# WordClock.net
KiCad netlist of a schematic drawn in EAGLE
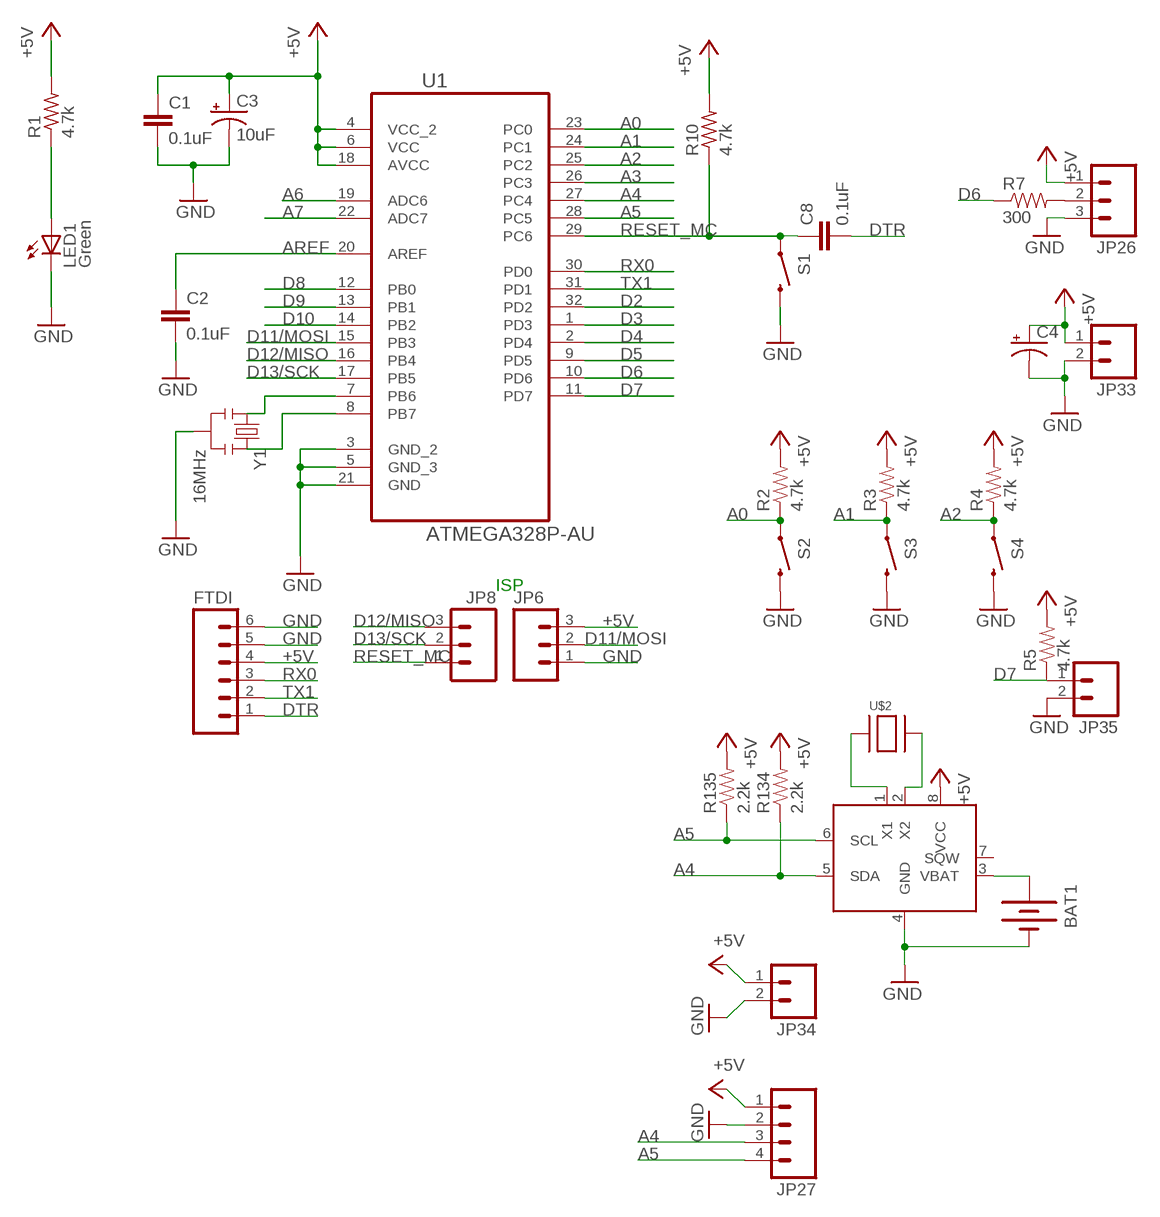
[diagram p0: schematic, sheet 1, part 1 of 2]
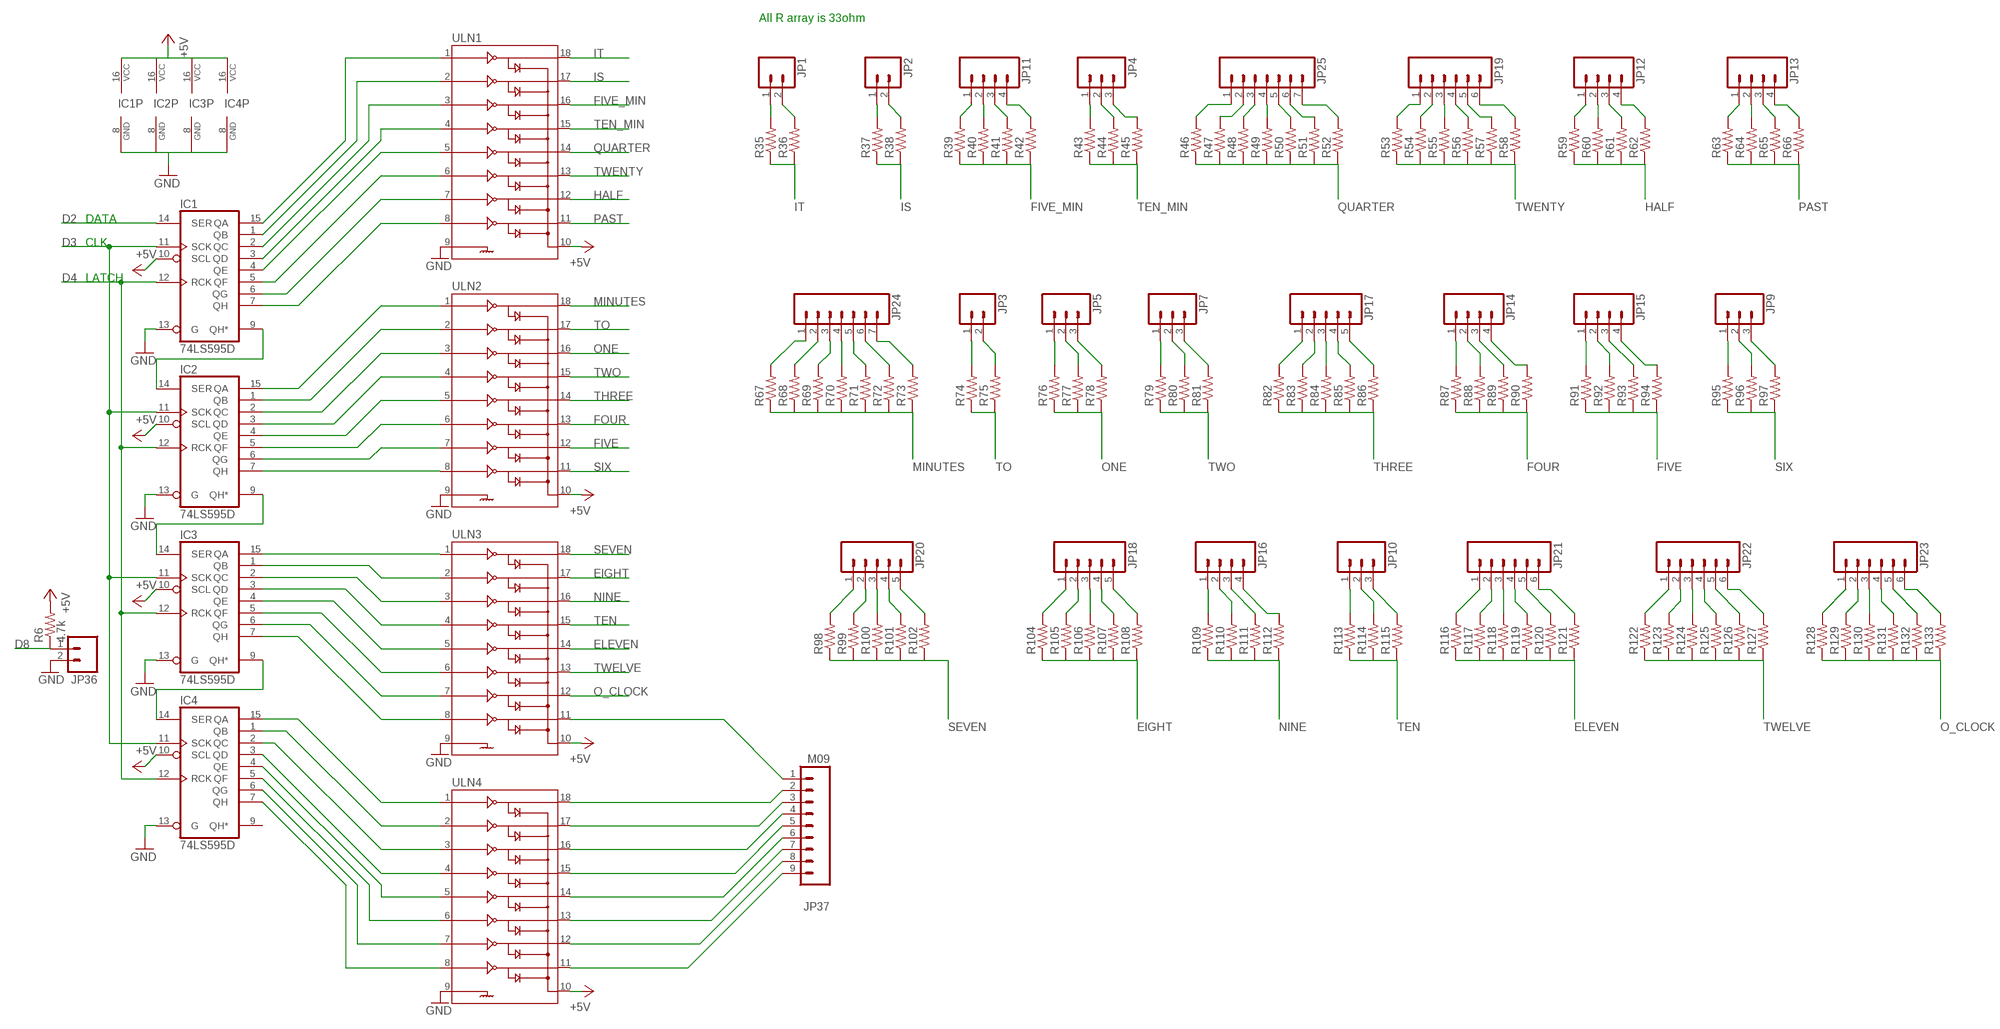
[diagram p1: schematic, sheet 1, part 2 of 2]

(export (version "E")
  (design (tool "Eeschema 10.0.6"))
  (components
    (comp (ref "BAT1")
      (value "BATTERY12MM")
      (footprint "eagle-import:BATTCON_12MM")
      (libsource (lib "eagle-import") (part "BATTERY12MM"))
    )
    (comp (ref "C1")
      (value "0.1uF")
      (footprint "eagle-import:0402-CAP")
      (libsource (lib "eagle-import") (part "CAP0402-CAP"))
    )
    (comp (ref "C2")
      (value "0.1uF")
      (footprint "eagle-import:0402-CAP")
      (libsource (lib "eagle-import") (part "CAP0402-CAP"))
    )
    (comp (ref "C3")
      (value "10uF")
      (footprint "eagle-import:EIA3216")
      (libsource (lib "eagle-import") (part "CAP_POL1206"))
    )
    (comp (ref "C4")
      (value "CPOL-USF")
      (footprint "eagle-import:PANASONIC_F")
      (libsource (lib "eagle-import") (part "CPOL-USF"))
    )
    (comp (ref "C8")
      (value "0.1uF")
      (footprint "eagle-import:0402-CAP")
      (libsource (lib "eagle-import") (part "CAP0402-CAP"))
    )
    (comp (ref "FTDI")
      (value "M06SIP")
      (footprint "eagle-import:1X06")
      (libsource (lib "eagle-import") (part "M06SIP"))
    )
    (comp (ref "IC1")
      (value "74LS595D")
      (footprint "eagle-import:SO16")
      (libsource (lib "eagle-import") (part "74595DLS"))
    )
    (comp (ref "IC2")
      (value "74LS595D")
      (footprint "eagle-import:SO16")
      (libsource (lib "eagle-import") (part "74595DLS"))
    )
    (comp (ref "IC3")
      (value "74LS595D")
      (footprint "eagle-import:SO16")
      (libsource (lib "eagle-import") (part "74595DLS"))
    )
    (comp (ref "IC4")
      (value "74LS595D")
      (footprint "eagle-import:SO16")
      (libsource (lib "eagle-import") (part "74595DLS"))
    )
    (comp (ref "JP1")
      (value "M02PTH")
      (footprint "eagle-import:1X02")
      (libsource (lib "eagle-import") (part "M02PTH"))
    )
    (comp (ref "JP2")
      (value "M02PTH")
      (footprint "eagle-import:1X02")
      (libsource (lib "eagle-import") (part "M02PTH"))
    )
    (comp (ref "JP3")
      (value "M02PTH")
      (footprint "eagle-import:1X02")
      (libsource (lib "eagle-import") (part "M02PTH"))
    )
    (comp (ref "JP4")
      (value "M03PTH")
      (footprint "eagle-import:1X03")
      (libsource (lib "eagle-import") (part "M03PTH"))
    )
    (comp (ref "JP5")
      (value "M03PTH")
      (footprint "eagle-import:1X03")
      (libsource (lib "eagle-import") (part "M03PTH"))
    )
    (comp (ref "JP6")
      (value "M03PTH")
      (footprint "eagle-import:1X03")
      (libsource (lib "eagle-import") (part "M03PTH"))
    )
    (comp (ref "JP7")
      (value "M03PTH")
      (footprint "eagle-import:1X03")
      (libsource (lib "eagle-import") (part "M03PTH"))
    )
    (comp (ref "JP8")
      (value "M03PTH")
      (footprint "eagle-import:1X03")
      (libsource (lib "eagle-import") (part "M03PTH"))
    )
    (comp (ref "JP9")
      (value "M03PTH")
      (footprint "eagle-import:1X03")
      (libsource (lib "eagle-import") (part "M03PTH"))
    )
    (comp (ref "JP10")
      (value "M03PTH")
      (footprint "eagle-import:1X03")
      (libsource (lib "eagle-import") (part "M03PTH"))
    )
    (comp (ref "JP11")
      (value "M04PTH")
      (footprint "eagle-import:1X04")
      (libsource (lib "eagle-import") (part "M04PTH"))
    )
    (comp (ref "JP12")
      (value "M04PTH")
      (footprint "eagle-import:1X04")
      (libsource (lib "eagle-import") (part "M04PTH"))
    )
    (comp (ref "JP13")
      (value "M04PTH")
      (footprint "eagle-import:1X04")
      (libsource (lib "eagle-import") (part "M04PTH"))
    )
    (comp (ref "JP14")
      (value "M04PTH")
      (footprint "eagle-import:1X04")
      (libsource (lib "eagle-import") (part "M04PTH"))
    )
    (comp (ref "JP15")
      (value "M04PTH")
      (footprint "eagle-import:1X04")
      (libsource (lib "eagle-import") (part "M04PTH"))
    )
    (comp (ref "JP16")
      (value "M04PTH")
      (footprint "eagle-import:1X04")
      (libsource (lib "eagle-import") (part "M04PTH"))
    )
    (comp (ref "JP17")
      (value "M05PTH")
      (footprint "eagle-import:1X05")
      (libsource (lib "eagle-import") (part "M05PTH"))
    )
    (comp (ref "JP18")
      (value "M05PTH")
      (footprint "eagle-import:1X05")
      (libsource (lib "eagle-import") (part "M05PTH"))
    )
    (comp (ref "JP19")
      (value "M06SIP")
      (footprint "eagle-import:1X06")
      (libsource (lib "eagle-import") (part "M06SIP"))
    )
    (comp (ref "JP20")
      (value "M05PTH")
      (footprint "eagle-import:1X05")
      (libsource (lib "eagle-import") (part "M05PTH"))
    )
    (comp (ref "JP21")
      (value "M06SIP")
      (footprint "eagle-import:1X06")
      (libsource (lib "eagle-import") (part "M06SIP"))
    )
    (comp (ref "JP22")
      (value "M06SIP")
      (footprint "eagle-import:1X06")
      (libsource (lib "eagle-import") (part "M06SIP"))
    )
    (comp (ref "JP23")
      (value "M06SIP")
      (footprint "eagle-import:1X06")
      (libsource (lib "eagle-import") (part "M06SIP"))
    )
    (comp (ref "JP24")
      (value "M07")
      (footprint "eagle-import:1X07")
      (libsource (lib "eagle-import") (part "M07"))
    )
    (comp (ref "JP25")
      (value "M07")
      (footprint "eagle-import:1X07")
      (libsource (lib "eagle-import") (part "M07"))
    )
    (comp (ref "JP26")
      (value "M03PTH")
      (footprint "eagle-import:1X03")
      (libsource (lib "eagle-import") (part "M03PTH"))
    )
    (comp (ref "JP27")
      (value "M04PTH")
      (footprint "eagle-import:1X04")
      (libsource (lib "eagle-import") (part "M04PTH"))
    )
    (comp (ref "JP33")
      (value "M02PTH")
      (footprint "eagle-import:1X02")
      (libsource (lib "eagle-import") (part "M02PTH"))
    )
    (comp (ref "JP34")
      (value "M02PTH")
      (footprint "eagle-import:1X02")
      (libsource (lib "eagle-import") (part "M02PTH"))
    )
    (comp (ref "JP35")
      (value "M02PTH")
      (footprint "eagle-import:1X02")
      (libsource (lib "eagle-import") (part "M02PTH"))
    )
    (comp (ref "JP36")
      (value "M02PTH")
      (footprint "eagle-import:1X02")
      (libsource (lib "eagle-import") (part "M02PTH"))
    )
    (comp (ref "JP37")
      (value "M09")
      (footprint "eagle-import:1X09")
      (libsource (lib "eagle-import") (part "M09"))
    )
    (comp (ref "LED1")
      (value "Green")
      (footprint "eagle-import:LED-0603")
      (libsource (lib "eagle-import") (part "LED0603"))
    )
    (comp (ref "R1")
      (value "4.7k")
      (footprint "eagle-import:R0603")
      (libsource (lib "eagle-import") (part "R-US_R0603"))
    )
    (comp (ref "R2")
      (value "4.7k")
      (footprint "eagle-import:0603-RES")
      (libsource (lib "eagle-import") (part "RESISTOR0603-RES"))
    )
    (comp (ref "R3")
      (value "4.7k")
      (footprint "eagle-import:0603-RES")
      (libsource (lib "eagle-import") (part "RESISTOR0603-RES"))
    )
    (comp (ref "R4")
      (value "4.7k")
      (footprint "eagle-import:0603-RES")
      (libsource (lib "eagle-import") (part "RESISTOR0603-RES"))
    )
    (comp (ref "R5")
      (value "4.7k")
      (footprint "eagle-import:0603-RES")
      (libsource (lib "eagle-import") (part "RESISTOR0603-RES"))
    )
    (comp (ref "R6")
      (value "4.7k")
      (footprint "eagle-import:0603-RES")
      (libsource (lib "eagle-import") (part "RESISTOR0603-RES"))
    )
    (comp (ref "R7")
      (value "300")
      (footprint "eagle-import:0603-RES")
      (libsource (lib "eagle-import") (part "RESISTOR0603-RES"))
    )
    (comp (ref "R10")
      (value "4.7k")
      (footprint "eagle-import:R0603")
      (libsource (lib "eagle-import") (part "R-US_R0603"))
    )
    (comp (ref "R35")
      (value "RESISTOR0603-RES")
      (footprint "eagle-import:0603-RES")
      (libsource (lib "eagle-import") (part "RESISTOR0603-RES"))
    )
    (comp (ref "R36")
      (value "RESISTOR0603-RES")
      (footprint "eagle-import:0603-RES")
      (libsource (lib "eagle-import") (part "RESISTOR0603-RES"))
    )
    (comp (ref "R37")
      (value "RESISTOR0603-RES")
      (footprint "eagle-import:0603-RES")
      (libsource (lib "eagle-import") (part "RESISTOR0603-RES"))
    )
    (comp (ref "R38")
      (value "RESISTOR0603-RES")
      (footprint "eagle-import:0603-RES")
      (libsource (lib "eagle-import") (part "RESISTOR0603-RES"))
    )
    (comp (ref "R39")
      (value "RESISTOR0603-RES")
      (footprint "eagle-import:0603-RES")
      (libsource (lib "eagle-import") (part "RESISTOR0603-RES"))
    )
    (comp (ref "R40")
      (value "RESISTOR0603-RES")
      (footprint "eagle-import:0603-RES")
      (libsource (lib "eagle-import") (part "RESISTOR0603-RES"))
    )
    (comp (ref "R41")
      (value "RESISTOR0603-RES")
      (footprint "eagle-import:0603-RES")
      (libsource (lib "eagle-import") (part "RESISTOR0603-RES"))
    )
    (comp (ref "R42")
      (value "RESISTOR0603-RES")
      (footprint "eagle-import:0603-RES")
      (libsource (lib "eagle-import") (part "RESISTOR0603-RES"))
    )
    (comp (ref "R43")
      (value "RESISTOR0603-RES")
      (footprint "eagle-import:0603-RES")
      (libsource (lib "eagle-import") (part "RESISTOR0603-RES"))
    )
    (comp (ref "R44")
      (value "RESISTOR0603-RES")
      (footprint "eagle-import:0603-RES")
      (libsource (lib "eagle-import") (part "RESISTOR0603-RES"))
    )
    (comp (ref "R45")
      (value "RESISTOR0603-RES")
      (footprint "eagle-import:0603-RES")
      (libsource (lib "eagle-import") (part "RESISTOR0603-RES"))
    )
    (comp (ref "R46")
      (value "RESISTOR0603-RES")
      (footprint "eagle-import:0603-RES")
      (libsource (lib "eagle-import") (part "RESISTOR0603-RES"))
    )
    (comp (ref "R47")
      (value "RESISTOR0603-RES")
      (footprint "eagle-import:0603-RES")
      (libsource (lib "eagle-import") (part "RESISTOR0603-RES"))
    )
    (comp (ref "R48")
      (value "RESISTOR0603-RES")
      (footprint "eagle-import:0603-RES")
      (libsource (lib "eagle-import") (part "RESISTOR0603-RES"))
    )
    (comp (ref "R49")
      (value "RESISTOR0603-RES")
      (footprint "eagle-import:0603-RES")
      (libsource (lib "eagle-import") (part "RESISTOR0603-RES"))
    )
    (comp (ref "R50")
      (value "RESISTOR0603-RES")
      (footprint "eagle-import:0603-RES")
      (libsource (lib "eagle-import") (part "RESISTOR0603-RES"))
    )
    (comp (ref "R51")
      (value "RESISTOR0603-RES")
      (footprint "eagle-import:0603-RES")
      (libsource (lib "eagle-import") (part "RESISTOR0603-RES"))
    )
    (comp (ref "R52")
      (value "RESISTOR0603-RES")
      (footprint "eagle-import:0603-RES")
      (libsource (lib "eagle-import") (part "RESISTOR0603-RES"))
    )
    (comp (ref "R53")
      (value "RESISTOR0603-RES")
      (footprint "eagle-import:0603-RES")
      (libsource (lib "eagle-import") (part "RESISTOR0603-RES"))
    )
    (comp (ref "R54")
      (value "RESISTOR0603-RES")
      (footprint "eagle-import:0603-RES")
      (libsource (lib "eagle-import") (part "RESISTOR0603-RES"))
    )
    (comp (ref "R55")
      (value "RESISTOR0603-RES")
      (footprint "eagle-import:0603-RES")
      (libsource (lib "eagle-import") (part "RESISTOR0603-RES"))
    )
    (comp (ref "R56")
      (value "RESISTOR0603-RES")
      (footprint "eagle-import:0603-RES")
      (libsource (lib "eagle-import") (part "RESISTOR0603-RES"))
    )
    (comp (ref "R57")
      (value "RESISTOR0603-RES")
      (footprint "eagle-import:0603-RES")
      (libsource (lib "eagle-import") (part "RESISTOR0603-RES"))
    )
    (comp (ref "R58")
      (value "RESISTOR0603-RES")
      (footprint "eagle-import:0603-RES")
      (libsource (lib "eagle-import") (part "RESISTOR0603-RES"))
    )
    (comp (ref "R59")
      (value "RESISTOR0603-RES")
      (footprint "eagle-import:0603-RES")
      (libsource (lib "eagle-import") (part "RESISTOR0603-RES"))
    )
    (comp (ref "R60")
      (value "RESISTOR0603-RES")
      (footprint "eagle-import:0603-RES")
      (libsource (lib "eagle-import") (part "RESISTOR0603-RES"))
    )
    (comp (ref "R61")
      (value "RESISTOR0603-RES")
      (footprint "eagle-import:0603-RES")
      (libsource (lib "eagle-import") (part "RESISTOR0603-RES"))
    )
    (comp (ref "R62")
      (value "RESISTOR0603-RES")
      (footprint "eagle-import:0603-RES")
      (libsource (lib "eagle-import") (part "RESISTOR0603-RES"))
    )
    (comp (ref "R63")
      (value "RESISTOR0603-RES")
      (footprint "eagle-import:0603-RES")
      (libsource (lib "eagle-import") (part "RESISTOR0603-RES"))
    )
    (comp (ref "R64")
      (value "RESISTOR0603-RES")
      (footprint "eagle-import:0603-RES")
      (libsource (lib "eagle-import") (part "RESISTOR0603-RES"))
    )
    (comp (ref "R65")
      (value "RESISTOR0603-RES")
      (footprint "eagle-import:0603-RES")
      (libsource (lib "eagle-import") (part "RESISTOR0603-RES"))
    )
    (comp (ref "R66")
      (value "RESISTOR0603-RES")
      (footprint "eagle-import:0603-RES")
      (libsource (lib "eagle-import") (part "RESISTOR0603-RES"))
    )
    (comp (ref "R67")
      (value "RESISTOR0603-RES")
      (footprint "eagle-import:0603-RES")
      (libsource (lib "eagle-import") (part "RESISTOR0603-RES"))
    )
    (comp (ref "R68")
      (value "RESISTOR0603-RES")
      (footprint "eagle-import:0603-RES")
      (libsource (lib "eagle-import") (part "RESISTOR0603-RES"))
    )
    (comp (ref "R69")
      (value "RESISTOR0603-RES")
      (footprint "eagle-import:0603-RES")
      (libsource (lib "eagle-import") (part "RESISTOR0603-RES"))
    )
    (comp (ref "R70")
      (value "RESISTOR0603-RES")
      (footprint "eagle-import:0603-RES")
      (libsource (lib "eagle-import") (part "RESISTOR0603-RES"))
    )
    (comp (ref "R71")
      (value "RESISTOR0603-RES")
      (footprint "eagle-import:0603-RES")
      (libsource (lib "eagle-import") (part "RESISTOR0603-RES"))
    )
    (comp (ref "R72")
      (value "RESISTOR0603-RES")
      (footprint "eagle-import:0603-RES")
      (libsource (lib "eagle-import") (part "RESISTOR0603-RES"))
    )
    (comp (ref "R73")
      (value "RESISTOR0603-RES")
      (footprint "eagle-import:0603-RES")
      (libsource (lib "eagle-import") (part "RESISTOR0603-RES"))
    )
    (comp (ref "R74")
      (value "RESISTOR0603-RES")
      (footprint "eagle-import:0603-RES")
      (libsource (lib "eagle-import") (part "RESISTOR0603-RES"))
    )
    (comp (ref "R75")
      (value "RESISTOR0603-RES")
      (footprint "eagle-import:0603-RES")
      (libsource (lib "eagle-import") (part "RESISTOR0603-RES"))
    )
    (comp (ref "R76")
      (value "RESISTOR0603-RES")
      (footprint "eagle-import:0603-RES")
      (libsource (lib "eagle-import") (part "RESISTOR0603-RES"))
    )
    (comp (ref "R77")
      (value "RESISTOR0603-RES")
      (footprint "eagle-import:0603-RES")
      (libsource (lib "eagle-import") (part "RESISTOR0603-RES"))
    )
    (comp (ref "R78")
      (value "RESISTOR0603-RES")
      (footprint "eagle-import:0603-RES")
      (libsource (lib "eagle-import") (part "RESISTOR0603-RES"))
    )
    (comp (ref "R79")
      (value "RESISTOR0603-RES")
      (footprint "eagle-import:0603-RES")
      (libsource (lib "eagle-import") (part "RESISTOR0603-RES"))
    )
    (comp (ref "R80")
      (value "RESISTOR0603-RES")
      (footprint "eagle-import:0603-RES")
      (libsource (lib "eagle-import") (part "RESISTOR0603-RES"))
    )
    (comp (ref "R81")
      (value "RESISTOR0603-RES")
      (footprint "eagle-import:0603-RES")
      (libsource (lib "eagle-import") (part "RESISTOR0603-RES"))
    )
    (comp (ref "R82")
      (value "RESISTOR0603-RES")
      (footprint "eagle-import:0603-RES")
      (libsource (lib "eagle-import") (part "RESISTOR0603-RES"))
    )
    (comp (ref "R83")
      (value "RESISTOR0603-RES")
      (footprint "eagle-import:0603-RES")
      (libsource (lib "eagle-import") (part "RESISTOR0603-RES"))
    )
    (comp (ref "R84")
      (value "RESISTOR0603-RES")
      (footprint "eagle-import:0603-RES")
      (libsource (lib "eagle-import") (part "RESISTOR0603-RES"))
    )
    (comp (ref "R85")
      (value "RESISTOR0603-RES")
      (footprint "eagle-import:0603-RES")
      (libsource (lib "eagle-import") (part "RESISTOR0603-RES"))
    )
    (comp (ref "R86")
      (value "RESISTOR0603-RES")
      (footprint "eagle-import:0603-RES")
      (libsource (lib "eagle-import") (part "RESISTOR0603-RES"))
    )
    (comp (ref "R87")
      (value "RESISTOR0603-RES")
      (footprint "eagle-import:0603-RES")
      (libsource (lib "eagle-import") (part "RESISTOR0603-RES"))
    )
    (comp (ref "R88")
      (value "RESISTOR0603-RES")
      (footprint "eagle-import:0603-RES")
      (libsource (lib "eagle-import") (part "RESISTOR0603-RES"))
    )
    (comp (ref "R89")
      (value "RESISTOR0603-RES")
      (footprint "eagle-import:0603-RES")
      (libsource (lib "eagle-import") (part "RESISTOR0603-RES"))
    )
    (comp (ref "R90")
      (value "RESISTOR0603-RES")
      (footprint "eagle-import:0603-RES")
      (libsource (lib "eagle-import") (part "RESISTOR0603-RES"))
    )
    (comp (ref "R91")
      (value "RESISTOR0603-RES")
      (footprint "eagle-import:0603-RES")
      (libsource (lib "eagle-import") (part "RESISTOR0603-RES"))
    )
    (comp (ref "R92")
      (value "RESISTOR0603-RES")
      (footprint "eagle-import:0603-RES")
      (libsource (lib "eagle-import") (part "RESISTOR0603-RES"))
    )
    (comp (ref "R93")
      (value "RESISTOR0603-RES")
      (footprint "eagle-import:0603-RES")
      (libsource (lib "eagle-import") (part "RESISTOR0603-RES"))
    )
    (comp (ref "R94")
      (value "RESISTOR0603-RES")
      (footprint "eagle-import:0603-RES")
      (libsource (lib "eagle-import") (part "RESISTOR0603-RES"))
    )
    (comp (ref "R95")
      (value "RESISTOR0603-RES")
      (footprint "eagle-import:0603-RES")
      (libsource (lib "eagle-import") (part "RESISTOR0603-RES"))
    )
    (comp (ref "R96")
      (value "RESISTOR0603-RES")
      (footprint "eagle-import:0603-RES")
      (libsource (lib "eagle-import") (part "RESISTOR0603-RES"))
    )
    (comp (ref "R97")
      (value "RESISTOR0603-RES")
      (footprint "eagle-import:0603-RES")
      (libsource (lib "eagle-import") (part "RESISTOR0603-RES"))
    )
    (comp (ref "R98")
      (value "RESISTOR0603-RES")
      (footprint "eagle-import:0603-RES")
      (libsource (lib "eagle-import") (part "RESISTOR0603-RES"))
    )
    (comp (ref "R99")
      (value "RESISTOR0603-RES")
      (footprint "eagle-import:0603-RES")
      (libsource (lib "eagle-import") (part "RESISTOR0603-RES"))
    )
    (comp (ref "R100")
      (value "RESISTOR0603-RES")
      (footprint "eagle-import:0603-RES")
      (libsource (lib "eagle-import") (part "RESISTOR0603-RES"))
    )
    (comp (ref "R101")
      (value "RESISTOR0603-RES")
      (footprint "eagle-import:0603-RES")
      (libsource (lib "eagle-import") (part "RESISTOR0603-RES"))
    )
    (comp (ref "R102")
      (value "RESISTOR0603-RES")
      (footprint "eagle-import:0603-RES")
      (libsource (lib "eagle-import") (part "RESISTOR0603-RES"))
    )
    (comp (ref "R104")
      (value "RESISTOR0603-RES")
      (footprint "eagle-import:0603-RES")
      (libsource (lib "eagle-import") (part "RESISTOR0603-RES"))
    )
    (comp (ref "R105")
      (value "RESISTOR0603-RES")
      (footprint "eagle-import:0603-RES")
      (libsource (lib "eagle-import") (part "RESISTOR0603-RES"))
    )
    (comp (ref "R106")
      (value "RESISTOR0603-RES")
      (footprint "eagle-import:0603-RES")
      (libsource (lib "eagle-import") (part "RESISTOR0603-RES"))
    )
    (comp (ref "R107")
      (value "RESISTOR0603-RES")
      (footprint "eagle-import:0603-RES")
      (libsource (lib "eagle-import") (part "RESISTOR0603-RES"))
    )
    (comp (ref "R108")
      (value "RESISTOR0603-RES")
      (footprint "eagle-import:0603-RES")
      (libsource (lib "eagle-import") (part "RESISTOR0603-RES"))
    )
    (comp (ref "R109")
      (value "RESISTOR0603-RES")
      (footprint "eagle-import:0603-RES")
      (libsource (lib "eagle-import") (part "RESISTOR0603-RES"))
    )
    (comp (ref "R110")
      (value "RESISTOR0603-RES")
      (footprint "eagle-import:0603-RES")
      (libsource (lib "eagle-import") (part "RESISTOR0603-RES"))
    )
    (comp (ref "R111")
      (value "RESISTOR0603-RES")
      (footprint "eagle-import:0603-RES")
      (libsource (lib "eagle-import") (part "RESISTOR0603-RES"))
    )
    (comp (ref "R112")
      (value "RESISTOR0603-RES")
      (footprint "eagle-import:0603-RES")
      (libsource (lib "eagle-import") (part "RESISTOR0603-RES"))
    )
    (comp (ref "R113")
      (value "RESISTOR0603-RES")
      (footprint "eagle-import:0603-RES")
      (libsource (lib "eagle-import") (part "RESISTOR0603-RES"))
    )
    (comp (ref "R114")
      (value "RESISTOR0603-RES")
      (footprint "eagle-import:0603-RES")
      (libsource (lib "eagle-import") (part "RESISTOR0603-RES"))
    )
    (comp (ref "R115")
      (value "RESISTOR0603-RES")
      (footprint "eagle-import:0603-RES")
      (libsource (lib "eagle-import") (part "RESISTOR0603-RES"))
    )
    (comp (ref "R116")
      (value "RESISTOR0603-RES")
      (footprint "eagle-import:0603-RES")
      (libsource (lib "eagle-import") (part "RESISTOR0603-RES"))
    )
    (comp (ref "R117")
      (value "RESISTOR0603-RES")
      (footprint "eagle-import:0603-RES")
      (libsource (lib "eagle-import") (part "RESISTOR0603-RES"))
    )
    (comp (ref "R118")
      (value "RESISTOR0603-RES")
      (footprint "eagle-import:0603-RES")
      (libsource (lib "eagle-import") (part "RESISTOR0603-RES"))
    )
    (comp (ref "R119")
      (value "RESISTOR0603-RES")
      (footprint "eagle-import:0603-RES")
      (libsource (lib "eagle-import") (part "RESISTOR0603-RES"))
    )
    (comp (ref "R120")
      (value "RESISTOR0603-RES")
      (footprint "eagle-import:0603-RES")
      (libsource (lib "eagle-import") (part "RESISTOR0603-RES"))
    )
    (comp (ref "R121")
      (value "RESISTOR0603-RES")
      (footprint "eagle-import:0603-RES")
      (libsource (lib "eagle-import") (part "RESISTOR0603-RES"))
    )
    (comp (ref "R122")
      (value "RESISTOR0603-RES")
      (footprint "eagle-import:0603-RES")
      (libsource (lib "eagle-import") (part "RESISTOR0603-RES"))
    )
    (comp (ref "R123")
      (value "RESISTOR0603-RES")
      (footprint "eagle-import:0603-RES")
      (libsource (lib "eagle-import") (part "RESISTOR0603-RES"))
    )
    (comp (ref "R124")
      (value "RESISTOR0603-RES")
      (footprint "eagle-import:0603-RES")
      (libsource (lib "eagle-import") (part "RESISTOR0603-RES"))
    )
    (comp (ref "R125")
      (value "RESISTOR0603-RES")
      (footprint "eagle-import:0603-RES")
      (libsource (lib "eagle-import") (part "RESISTOR0603-RES"))
    )
    (comp (ref "R126")
      (value "RESISTOR0603-RES")
      (footprint "eagle-import:0603-RES")
      (libsource (lib "eagle-import") (part "RESISTOR0603-RES"))
    )
    (comp (ref "R127")
      (value "RESISTOR0603-RES")
      (footprint "eagle-import:0603-RES")
      (libsource (lib "eagle-import") (part "RESISTOR0603-RES"))
    )
    (comp (ref "R128")
      (value "RESISTOR0603-RES")
      (footprint "eagle-import:0603-RES")
      (libsource (lib "eagle-import") (part "RESISTOR0603-RES"))
    )
    (comp (ref "R129")
      (value "RESISTOR0603-RES")
      (footprint "eagle-import:0603-RES")
      (libsource (lib "eagle-import") (part "RESISTOR0603-RES"))
    )
    (comp (ref "R130")
      (value "RESISTOR0603-RES")
      (footprint "eagle-import:0603-RES")
      (libsource (lib "eagle-import") (part "RESISTOR0603-RES"))
    )
    (comp (ref "R131")
      (value "RESISTOR0603-RES")
      (footprint "eagle-import:0603-RES")
      (libsource (lib "eagle-import") (part "RESISTOR0603-RES"))
    )
    (comp (ref "R132")
      (value "RESISTOR0603-RES")
      (footprint "eagle-import:0603-RES")
      (libsource (lib "eagle-import") (part "RESISTOR0603-RES"))
    )
    (comp (ref "R133")
      (value "RESISTOR0603-RES")
      (footprint "eagle-import:0603-RES")
      (libsource (lib "eagle-import") (part "RESISTOR0603-RES"))
    )
    (comp (ref "R134")
      (value "2.2k")
      (footprint "eagle-import:0603-RES")
      (libsource (lib "eagle-import") (part "RESISTOR0603-RES"))
    )
    (comp (ref "R135")
      (value "2.2k")
      (footprint "eagle-import:0603-RES")
      (libsource (lib "eagle-import") (part "RESISTOR0603-RES"))
    )
    (comp (ref "S1")
      (value "SWITCH-MOMENTARY-2")
      (footprint "eagle-import:TACTILE_SWITCH_TALL")
      (libsource (lib "eagle-import") (part "SWITCH-MOMENTARY-2"))
    )
    (comp (ref "S2")
      (value "SWITCH-MOMENTARY-2")
      (footprint "eagle-import:TACTILE_SWITCH_TALL")
      (libsource (lib "eagle-import") (part "SWITCH-MOMENTARY-2"))
    )
    (comp (ref "S3")
      (value "SWITCH-MOMENTARY-2")
      (footprint "eagle-import:TACTILE_SWITCH_TALL")
      (libsource (lib "eagle-import") (part "SWITCH-MOMENTARY-2"))
    )
    (comp (ref "S4")
      (value "SWITCH-MOMENTARY-2")
      (footprint "eagle-import:TACTILE_SWITCH_TALL")
      (libsource (lib "eagle-import") (part "SWITCH-MOMENTARY-2"))
    )
    (comp (ref "U$1")
      (value "DS1307")
      (footprint "eagle-import:8-SOIC")
      (libsource (lib "eagle-import") (part "DS1307"))
    )
    (comp (ref "U$2")
      (value "CRYSTAL-32.768K")
      (footprint "eagle-import:4-SOJ")
      (libsource (lib "eagle-import") (part "CRYSTAL-32.768K"))
    )
    (comp (ref "U1")
      (value "ATMEGA328P-AU")
      (footprint "eagle-import:QFP80P900X900X120-32N")
      (libsource (lib "eagle-import") (part "ATMEGA328P-AU"))
    )
    (comp (ref "ULN1")
      (value "ULN2803SOICW")
      (footprint "eagle-import:SO18L")
      (libsource (lib "eagle-import") (part "ULN2803SOICW"))
    )
    (comp (ref "ULN2")
      (value "ULN2803SOICW")
      (footprint "eagle-import:SO18L")
      (libsource (lib "eagle-import") (part "ULN2803SOICW"))
    )
    (comp (ref "ULN3")
      (value "ULN2803SOICW")
      (footprint "eagle-import:SO18L")
      (libsource (lib "eagle-import") (part "ULN2803SOICW"))
    )
    (comp (ref "ULN4")
      (value "ULN2803SOICW")
      (footprint "eagle-import:SO18L")
      (libsource (lib "eagle-import") (part "ULN2803SOICW"))
    )
    (comp (ref "Y1")
      (value "16MHz")
      (footprint "eagle-import:RESONATOR-SMD")
      (libsource (lib "eagle-import") (part "RESONATORSMD"))
    )
  )
  (nets
    (net (code "1") (name "+5V") (class "Default")
      (node (ref "C1") (pin "1") (pinfunction "1_1") (pintype "passive"))
      (node (ref "C3") (pin "A") (pinfunction "+_A") (pintype "passive"))
      (node (ref "C4") (pin "+") (pinfunction "+_+") (pintype "passive"))
      (node (ref "FTDI") (pin "4") (pinfunction "4_4") (pintype "passive"))
      (node (ref "IC1") (pin "10") (pinfunction "SCL_10") (pintype "input"))
      (node (ref "IC1") (pin "16") (pinfunction "VCC_16") (pintype "power_in"))
      (node (ref "IC2") (pin "10") (pinfunction "SCL_10") (pintype "input"))
      (node (ref "IC2") (pin "16") (pinfunction "VCC_16") (pintype "power_in"))
      (node (ref "IC3") (pin "10") (pinfunction "SCL_10") (pintype "input"))
      (node (ref "IC3") (pin "16") (pinfunction "VCC_16") (pintype "power_in"))
      (node (ref "IC4") (pin "10") (pinfunction "SCL_10") (pintype "input"))
      (node (ref "IC4") (pin "16") (pinfunction "VCC_16") (pintype "power_in"))
      (node (ref "JP26") (pin "1") (pinfunction "1_1") (pintype "passive"))
      (node (ref "JP27") (pin "1") (pinfunction "1_1") (pintype "passive"))
      (node (ref "JP33") (pin "1") (pinfunction "1_1") (pintype "passive"))
      (node (ref "JP34") (pin "1") (pinfunction "1_1") (pintype "passive"))
      (node (ref "JP6") (pin "3") (pinfunction "3_3") (pintype "passive"))
      (node (ref "R1") (pin "2") (pinfunction "2_2") (pintype "passive"))
      (node (ref "R10") (pin "2") (pinfunction "2_2") (pintype "passive"))
      (node (ref "R134") (pin "2") (pinfunction "2_2") (pintype "passive"))
      (node (ref "R135") (pin "2") (pinfunction "2_2") (pintype "passive"))
      (node (ref "R2") (pin "2") (pinfunction "2_2") (pintype "passive"))
      (node (ref "R3") (pin "2") (pinfunction "2_2") (pintype "passive"))
      (node (ref "R4") (pin "2") (pinfunction "2_2") (pintype "passive"))
      (node (ref "R5") (pin "2") (pinfunction "2_2") (pintype "passive"))
      (node (ref "R6") (pin "2") (pinfunction "2_2") (pintype "passive"))
      (node (ref "U$1") (pin "8") (pinfunction "VCC_8") (pintype "bidirectional"))
      (node (ref "U1") (pin "18") (pinfunction "AVCC_18") (pintype "power_in"))
      (node (ref "U1") (pin "4") (pinfunction "VCC_2_4") (pintype "power_in"))
      (node (ref "U1") (pin "6") (pinfunction "VCC_6") (pintype "power_in"))
      (node (ref "ULN1") (pin "10") (pinfunction "10_10") (pintype "bidirectional"))
      (node (ref "ULN2") (pin "10") (pinfunction "10_10") (pintype "bidirectional"))
      (node (ref "ULN3") (pin "10") (pinfunction "10_10") (pintype "bidirectional"))
      (node (ref "ULN4") (pin "10") (pinfunction "10_10") (pintype "bidirectional"))
    )
    (net (code "2") (name "/A0") (class "Default")
      (node (ref "R2") (pin "1") (pinfunction "1_1") (pintype "passive"))
      (node (ref "S2") (pin "A2") (pinfunction "1_A2") (pintype "passive"))
      (node (ref "U1") (pin "23") (pinfunction "PC0_23") (pintype "bidirectional"))
    )
    (net (code "3") (name "/A1") (class "Default")
      (node (ref "R3") (pin "1") (pinfunction "1_1") (pintype "passive"))
      (node (ref "S3") (pin "A2") (pinfunction "1_A2") (pintype "passive"))
      (node (ref "U1") (pin "24") (pinfunction "PC1_24") (pintype "bidirectional"))
    )
    (net (code "4") (name "/A2") (class "Default")
      (node (ref "R4") (pin "1") (pinfunction "1_1") (pintype "passive"))
      (node (ref "S4") (pin "A2") (pinfunction "1_A2") (pintype "passive"))
      (node (ref "U1") (pin "25") (pinfunction "PC2_25") (pintype "bidirectional"))
    )
    (net (code "5") (name "/A3") (class "Default")
      (node (ref "U1") (pin "26") (pinfunction "PC3_26") (pintype "bidirectional"))
    )
    (net (code "6") (name "/A4") (class "Default")
      (node (ref "JP27") (pin "3") (pinfunction "3_3") (pintype "passive"))
      (node (ref "R134") (pin "1") (pinfunction "1_1") (pintype "passive"))
      (node (ref "U$1") (pin "5") (pinfunction "SDA_5") (pintype "bidirectional"))
      (node (ref "U1") (pin "27") (pinfunction "PC4_27") (pintype "bidirectional"))
    )
    (net (code "7") (name "/A5") (class "Default")
      (node (ref "JP27") (pin "4") (pinfunction "4_4") (pintype "passive"))
      (node (ref "R135") (pin "1") (pinfunction "1_1") (pintype "passive"))
      (node (ref "U$1") (pin "6") (pinfunction "SCL_6") (pintype "bidirectional"))
      (node (ref "U1") (pin "28") (pinfunction "PC5_28") (pintype "bidirectional"))
    )
    (net (code "8") (name "/A6") (class "Default")
      (node (ref "U1") (pin "19") (pinfunction "ADC6_19") (pintype "input"))
    )
    (net (code "9") (name "/A7") (class "Default")
      (node (ref "U1") (pin "22") (pinfunction "ADC7_22") (pintype "input"))
    )
    (net (code "10") (name "/AREF") (class "Default")
      (node (ref "C2") (pin "1") (pinfunction "1_1") (pintype "passive"))
      (node (ref "U1") (pin "20") (pinfunction "AREF_20") (pintype "input"))
    )
    (net (code "11") (name "/D2") (class "Default")
      (node (ref "IC1") (pin "14") (pinfunction "SER_14") (pintype "input"))
      (node (ref "U1") (pin "32") (pinfunction "PD2_32") (pintype "bidirectional"))
    )
    (net (code "12") (name "/D3") (class "Default")
      (node (ref "IC1") (pin "11") (pinfunction "SCK_11") (pintype "input"))
      (node (ref "IC2") (pin "11") (pinfunction "SCK_11") (pintype "input"))
      (node (ref "IC3") (pin "11") (pinfunction "SCK_11") (pintype "input"))
      (node (ref "IC4") (pin "11") (pinfunction "SCK_11") (pintype "input"))
      (node (ref "U1") (pin "1") (pinfunction "PD3_1") (pintype "bidirectional"))
    )
    (net (code "13") (name "/D4") (class "Default")
      (node (ref "IC1") (pin "12") (pinfunction "RCK_12") (pintype "input"))
      (node (ref "IC2") (pin "12") (pinfunction "RCK_12") (pintype "input"))
      (node (ref "IC3") (pin "12") (pinfunction "RCK_12") (pintype "input"))
      (node (ref "IC4") (pin "12") (pinfunction "RCK_12") (pintype "input"))
      (node (ref "U1") (pin "2") (pinfunction "PD4_2") (pintype "bidirectional"))
    )
    (net (code "14") (name "/D5") (class "Default")
      (node (ref "U1") (pin "9") (pinfunction "PD5_9") (pintype "bidirectional"))
    )
    (net (code "15") (name "/D6") (class "Default")
      (node (ref "R7") (pin "1") (pinfunction "1_1") (pintype "passive"))
      (node (ref "U1") (pin "10") (pinfunction "PD6_10") (pintype "bidirectional"))
    )
    (net (code "16") (name "/D7") (class "Default")
      (node (ref "JP35") (pin "1") (pinfunction "1_1") (pintype "passive"))
      (node (ref "R5") (pin "1") (pinfunction "1_1") (pintype "passive"))
      (node (ref "U1") (pin "11") (pinfunction "PD7_11") (pintype "bidirectional"))
    )
    (net (code "17") (name "/D8") (class "Default")
      (node (ref "JP36") (pin "1") (pinfunction "1_1") (pintype "passive"))
      (node (ref "R6") (pin "1") (pinfunction "1_1") (pintype "passive"))
      (node (ref "U1") (pin "12") (pinfunction "PB0_12") (pintype "bidirectional"))
    )
    (net (code "18") (name "/D9") (class "Default")
      (node (ref "U1") (pin "13") (pinfunction "PB1_13") (pintype "bidirectional"))
    )
    (net (code "19") (name "/D10") (class "Default")
      (node (ref "U1") (pin "14") (pinfunction "PB2_14") (pintype "bidirectional"))
    )
    (net (code "20") (name "/D11{slash}MOSI") (class "Default")
      (node (ref "JP6") (pin "2") (pinfunction "2_2") (pintype "passive"))
      (node (ref "U1") (pin "15") (pinfunction "PB3_15") (pintype "bidirectional"))
    )
    (net (code "21") (name "/D12{slash}MISO") (class "Default")
      (node (ref "JP8") (pin "3") (pinfunction "3_3") (pintype "passive"))
      (node (ref "U1") (pin "16") (pinfunction "PB4_16") (pintype "bidirectional"))
    )
    (net (code "22") (name "/D13{slash}SCK") (class "Default")
      (node (ref "JP8") (pin "2") (pinfunction "2_2") (pintype "passive"))
      (node (ref "U1") (pin "17") (pinfunction "PB5_17") (pintype "bidirectional"))
    )
    (net (code "23") (name "/DTR") (class "Default")
      (node (ref "C8") (pin "2") (pinfunction "2_2") (pintype "passive"))
      (node (ref "FTDI") (pin "1") (pinfunction "1_1") (pintype "passive"))
    )
    (net (code "24") (name "/EIGHT") (class "Default")
      (node (ref "R104") (pin "1") (pinfunction "1_1") (pintype "passive"))
      (node (ref "R105") (pin "1") (pinfunction "1_1") (pintype "passive"))
      (node (ref "R106") (pin "1") (pinfunction "1_1") (pintype "passive"))
      (node (ref "R107") (pin "1") (pinfunction "1_1") (pintype "passive"))
      (node (ref "R108") (pin "1") (pinfunction "1_1") (pintype "passive"))
      (node (ref "ULN3") (pin "17") (pinfunction "17_17") (pintype "bidirectional"))
    )
    (net (code "25") (name "/ELEVEN") (class "Default")
      (node (ref "R116") (pin "1") (pinfunction "1_1") (pintype "passive"))
      (node (ref "R117") (pin "1") (pinfunction "1_1") (pintype "passive"))
      (node (ref "R118") (pin "1") (pinfunction "1_1") (pintype "passive"))
      (node (ref "R119") (pin "1") (pinfunction "1_1") (pintype "passive"))
      (node (ref "R120") (pin "1") (pinfunction "1_1") (pintype "passive"))
      (node (ref "R121") (pin "1") (pinfunction "1_1") (pintype "passive"))
      (node (ref "ULN3") (pin "14") (pinfunction "14_14") (pintype "bidirectional"))
    )
    (net (code "26") (name "/FIVE") (class "Default")
      (node (ref "R91") (pin "1") (pinfunction "1_1") (pintype "passive"))
      (node (ref "R92") (pin "1") (pinfunction "1_1") (pintype "passive"))
      (node (ref "R93") (pin "1") (pinfunction "1_1") (pintype "passive"))
      (node (ref "R94") (pin "1") (pinfunction "1_1") (pintype "passive"))
      (node (ref "ULN2") (pin "12") (pinfunction "12_12") (pintype "bidirectional"))
    )
    (net (code "27") (name "/FIVE_MIN") (class "Default")
      (node (ref "R39") (pin "1") (pinfunction "1_1") (pintype "passive"))
      (node (ref "R40") (pin "1") (pinfunction "1_1") (pintype "passive"))
      (node (ref "R41") (pin "1") (pinfunction "1_1") (pintype "passive"))
      (node (ref "R42") (pin "1") (pinfunction "1_1") (pintype "passive"))
      (node (ref "ULN1") (pin "16") (pinfunction "16_16") (pintype "bidirectional"))
    )
    (net (code "28") (name "/FOUR") (class "Default")
      (node (ref "R87") (pin "1") (pinfunction "1_1") (pintype "passive"))
      (node (ref "R88") (pin "1") (pinfunction "1_1") (pintype "passive"))
      (node (ref "R89") (pin "1") (pinfunction "1_1") (pintype "passive"))
      (node (ref "R90") (pin "1") (pinfunction "1_1") (pintype "passive"))
      (node (ref "ULN2") (pin "13") (pinfunction "13_13") (pintype "bidirectional"))
    )
    (net (code "29") (name "/HALF") (class "Default")
      (node (ref "R59") (pin "1") (pinfunction "1_1") (pintype "passive"))
      (node (ref "R60") (pin "1") (pinfunction "1_1") (pintype "passive"))
      (node (ref "R61") (pin "1") (pinfunction "1_1") (pintype "passive"))
      (node (ref "R62") (pin "1") (pinfunction "1_1") (pintype "passive"))
      (node (ref "ULN1") (pin "12") (pinfunction "12_12") (pintype "bidirectional"))
    )
    (net (code "30") (name "/IS") (class "Default")
      (node (ref "R37") (pin "1") (pinfunction "1_1") (pintype "passive"))
      (node (ref "R38") (pin "1") (pinfunction "1_1") (pintype "passive"))
      (node (ref "ULN1") (pin "17") (pinfunction "17_17") (pintype "bidirectional"))
    )
    (net (code "31") (name "/IT") (class "Default")
      (node (ref "R35") (pin "1") (pinfunction "1_1") (pintype "passive"))
      (node (ref "R36") (pin "1") (pinfunction "1_1") (pintype "passive"))
      (node (ref "ULN1") (pin "18") (pinfunction "18_18") (pintype "bidirectional"))
    )
    (net (code "32") (name "/MINUTES") (class "Default")
      (node (ref "R67") (pin "1") (pinfunction "1_1") (pintype "passive"))
      (node (ref "R68") (pin "1") (pinfunction "1_1") (pintype "passive"))
      (node (ref "R69") (pin "1") (pinfunction "1_1") (pintype "passive"))
      (node (ref "R70") (pin "1") (pinfunction "1_1") (pintype "passive"))
      (node (ref "R71") (pin "1") (pinfunction "1_1") (pintype "passive"))
      (node (ref "R72") (pin "1") (pinfunction "1_1") (pintype "passive"))
      (node (ref "R73") (pin "1") (pinfunction "1_1") (pintype "passive"))
      (node (ref "ULN2") (pin "18") (pinfunction "18_18") (pintype "bidirectional"))
    )
    (net (code "33") (name "/NINE") (class "Default")
      (node (ref "R109") (pin "1") (pinfunction "1_1") (pintype "passive"))
      (node (ref "R110") (pin "1") (pinfunction "1_1") (pintype "passive"))
      (node (ref "R111") (pin "1") (pinfunction "1_1") (pintype "passive"))
      (node (ref "R112") (pin "1") (pinfunction "1_1") (pintype "passive"))
      (node (ref "ULN3") (pin "16") (pinfunction "16_16") (pintype "bidirectional"))
    )
    (net (code "34") (name "/ONE") (class "Default")
      (node (ref "R76") (pin "1") (pinfunction "1_1") (pintype "passive"))
      (node (ref "R77") (pin "1") (pinfunction "1_1") (pintype "passive"))
      (node (ref "R78") (pin "1") (pinfunction "1_1") (pintype "passive"))
      (node (ref "ULN2") (pin "16") (pinfunction "16_16") (pintype "bidirectional"))
    )
    (net (code "35") (name "/O_CLOCK") (class "Default")
      (node (ref "R128") (pin "1") (pinfunction "1_1") (pintype "passive"))
      (node (ref "R129") (pin "1") (pinfunction "1_1") (pintype "passive"))
      (node (ref "R130") (pin "1") (pinfunction "1_1") (pintype "passive"))
      (node (ref "R131") (pin "1") (pinfunction "1_1") (pintype "passive"))
      (node (ref "R132") (pin "1") (pinfunction "1_1") (pintype "passive"))
      (node (ref "R133") (pin "1") (pinfunction "1_1") (pintype "passive"))
      (node (ref "ULN3") (pin "12") (pinfunction "12_12") (pintype "bidirectional"))
    )
    (net (code "36") (name "/PAST") (class "Default")
      (node (ref "R63") (pin "1") (pinfunction "1_1") (pintype "passive"))
      (node (ref "R64") (pin "1") (pinfunction "1_1") (pintype "passive"))
      (node (ref "R65") (pin "1") (pinfunction "1_1") (pintype "passive"))
      (node (ref "R66") (pin "1") (pinfunction "1_1") (pintype "passive"))
      (node (ref "ULN1") (pin "11") (pinfunction "11_11") (pintype "bidirectional"))
    )
    (net (code "37") (name "/QUARTER") (class "Default")
      (node (ref "R46") (pin "1") (pinfunction "1_1") (pintype "passive"))
      (node (ref "R47") (pin "1") (pinfunction "1_1") (pintype "passive"))
      (node (ref "R48") (pin "1") (pinfunction "1_1") (pintype "passive"))
      (node (ref "R49") (pin "1") (pinfunction "1_1") (pintype "passive"))
      (node (ref "R50") (pin "1") (pinfunction "1_1") (pintype "passive"))
      (node (ref "R51") (pin "1") (pinfunction "1_1") (pintype "passive"))
      (node (ref "R52") (pin "1") (pinfunction "1_1") (pintype "passive"))
      (node (ref "ULN1") (pin "14") (pinfunction "14_14") (pintype "bidirectional"))
    )
    (net (code "38") (name "/RESET_MC") (class "Default")
      (node (ref "C8") (pin "1") (pinfunction "1_1") (pintype "passive"))
      (node (ref "JP8") (pin "1") (pinfunction "1_1") (pintype "passive"))
      (node (ref "R10") (pin "1") (pinfunction "1_1") (pintype "passive"))
      (node (ref "S1") (pin "A2") (pinfunction "1_A2") (pintype "passive"))
      (node (ref "U1") (pin "29") (pinfunction "PC6_29") (pintype "bidirectional"))
    )
    (net (code "39") (name "/RX0") (class "Default")
      (node (ref "FTDI") (pin "3") (pinfunction "3_3") (pintype "passive"))
      (node (ref "U1") (pin "30") (pinfunction "PD0_30") (pintype "bidirectional"))
    )
    (net (code "40") (name "/SEVEN") (class "Default")
      (node (ref "R100") (pin "1") (pinfunction "1_1") (pintype "passive"))
      (node (ref "R101") (pin "1") (pinfunction "1_1") (pintype "passive"))
      (node (ref "R102") (pin "1") (pinfunction "1_1") (pintype "passive"))
      (node (ref "R98") (pin "1") (pinfunction "1_1") (pintype "passive"))
      (node (ref "R99") (pin "1") (pinfunction "1_1") (pintype "passive"))
      (node (ref "ULN3") (pin "18") (pinfunction "18_18") (pintype "bidirectional"))
    )
    (net (code "41") (name "/SIX") (class "Default")
      (node (ref "R95") (pin "1") (pinfunction "1_1") (pintype "passive"))
      (node (ref "R96") (pin "1") (pinfunction "1_1") (pintype "passive"))
      (node (ref "R97") (pin "1") (pinfunction "1_1") (pintype "passive"))
      (node (ref "ULN2") (pin "11") (pinfunction "11_11") (pintype "bidirectional"))
    )
    (net (code "42") (name "/TEN") (class "Default")
      (node (ref "R113") (pin "1") (pinfunction "1_1") (pintype "passive"))
      (node (ref "R114") (pin "1") (pinfunction "1_1") (pintype "passive"))
      (node (ref "R115") (pin "1") (pinfunction "1_1") (pintype "passive"))
      (node (ref "ULN3") (pin "15") (pinfunction "15_15") (pintype "bidirectional"))
    )
    (net (code "43") (name "/TEN_MIN") (class "Default")
      (node (ref "R43") (pin "1") (pinfunction "1_1") (pintype "passive"))
      (node (ref "R44") (pin "1") (pinfunction "1_1") (pintype "passive"))
      (node (ref "R45") (pin "1") (pinfunction "1_1") (pintype "passive"))
      (node (ref "ULN1") (pin "15") (pinfunction "15_15") (pintype "bidirectional"))
    )
    (net (code "44") (name "/THREE") (class "Default")
      (node (ref "R82") (pin "1") (pinfunction "1_1") (pintype "passive"))
      (node (ref "R83") (pin "1") (pinfunction "1_1") (pintype "passive"))
      (node (ref "R84") (pin "1") (pinfunction "1_1") (pintype "passive"))
      (node (ref "R85") (pin "1") (pinfunction "1_1") (pintype "passive"))
      (node (ref "R86") (pin "1") (pinfunction "1_1") (pintype "passive"))
      (node (ref "ULN2") (pin "14") (pinfunction "14_14") (pintype "bidirectional"))
    )
    (net (code "45") (name "/TO") (class "Default")
      (node (ref "R74") (pin "1") (pinfunction "1_1") (pintype "passive"))
      (node (ref "R75") (pin "1") (pinfunction "1_1") (pintype "passive"))
      (node (ref "ULN2") (pin "17") (pinfunction "17_17") (pintype "bidirectional"))
    )
    (net (code "46") (name "/TWELVE") (class "Default")
      (node (ref "R122") (pin "1") (pinfunction "1_1") (pintype "passive"))
      (node (ref "R123") (pin "1") (pinfunction "1_1") (pintype "passive"))
      (node (ref "R124") (pin "1") (pinfunction "1_1") (pintype "passive"))
      (node (ref "R125") (pin "1") (pinfunction "1_1") (pintype "passive"))
      (node (ref "R126") (pin "1") (pinfunction "1_1") (pintype "passive"))
      (node (ref "R127") (pin "1") (pinfunction "1_1") (pintype "passive"))
      (node (ref "ULN3") (pin "13") (pinfunction "13_13") (pintype "bidirectional"))
    )
    (net (code "47") (name "/TWENTY") (class "Default")
      (node (ref "R53") (pin "1") (pinfunction "1_1") (pintype "passive"))
      (node (ref "R54") (pin "1") (pinfunction "1_1") (pintype "passive"))
      (node (ref "R55") (pin "1") (pinfunction "1_1") (pintype "passive"))
      (node (ref "R56") (pin "1") (pinfunction "1_1") (pintype "passive"))
      (node (ref "R57") (pin "1") (pinfunction "1_1") (pintype "passive"))
      (node (ref "R58") (pin "1") (pinfunction "1_1") (pintype "passive"))
      (node (ref "ULN1") (pin "13") (pinfunction "13_13") (pintype "bidirectional"))
    )
    (net (code "48") (name "/TWO") (class "Default")
      (node (ref "R79") (pin "1") (pinfunction "1_1") (pintype "passive"))
      (node (ref "R80") (pin "1") (pinfunction "1_1") (pintype "passive"))
      (node (ref "R81") (pin "1") (pinfunction "1_1") (pintype "passive"))
      (node (ref "ULN2") (pin "15") (pinfunction "15_15") (pintype "bidirectional"))
    )
    (net (code "49") (name "/TX1") (class "Default")
      (node (ref "FTDI") (pin "2") (pinfunction "2_2") (pintype "passive"))
      (node (ref "U1") (pin "31") (pinfunction "PD1_31") (pintype "bidirectional"))
    )
    (net (code "50") (name "GND") (class "Default")
      (node (ref "BAT1") (pin "GND") (pinfunction "-_GND") (pintype "power_in"))
      (node (ref "C1") (pin "2") (pinfunction "2_2") (pintype "passive"))
      (node (ref "C2") (pin "2") (pinfunction "2_2") (pintype "passive"))
      (node (ref "C3") (pin "C") (pinfunction "-_C") (pintype "passive"))
      (node (ref "C4") (pin "-") (pinfunction "-_-") (pintype "passive"))
      (node (ref "FTDI") (pin "5") (pinfunction "5_5") (pintype "passive"))
      (node (ref "FTDI") (pin "6") (pinfunction "6_6") (pintype "passive"))
      (node (ref "IC1") (pin "13") (pinfunction "G_13") (pintype "input"))
      (node (ref "IC1") (pin "8") (pinfunction "GND_8") (pintype "power_in"))
      (node (ref "IC2") (pin "13") (pinfunction "G_13") (pintype "input"))
      (node (ref "IC2") (pin "8") (pinfunction "GND_8") (pintype "power_in"))
      (node (ref "IC3") (pin "13") (pinfunction "G_13") (pintype "input"))
      (node (ref "IC3") (pin "8") (pinfunction "GND_8") (pintype "power_in"))
      (node (ref "IC4") (pin "13") (pinfunction "G_13") (pintype "input"))
      (node (ref "IC4") (pin "8") (pinfunction "GND_8") (pintype "power_in"))
      (node (ref "JP26") (pin "3") (pinfunction "3_3") (pintype "passive"))
      (node (ref "JP27") (pin "2") (pinfunction "2_2") (pintype "passive"))
      (node (ref "JP33") (pin "2") (pinfunction "2_2") (pintype "passive"))
      (node (ref "JP34") (pin "2") (pinfunction "2_2") (pintype "passive"))
      (node (ref "JP35") (pin "2") (pinfunction "2_2") (pintype "passive"))
      (node (ref "JP36") (pin "2") (pinfunction "2_2") (pintype "passive"))
      (node (ref "JP6") (pin "1") (pinfunction "1_1") (pintype "passive"))
      (node (ref "LED1") (pin "C") (pinfunction "C_C") (pintype "passive"))
      (node (ref "S1") (pin "B2") (pinfunction "2_B2") (pintype "passive"))
      (node (ref "S2") (pin "B2") (pinfunction "2_B2") (pintype "passive"))
      (node (ref "S3") (pin "B2") (pinfunction "2_B2") (pintype "passive"))
      (node (ref "S4") (pin "B2") (pinfunction "2_B2") (pintype "passive"))
      (node (ref "U$1") (pin "4") (pinfunction "GND_4") (pintype "bidirectional"))
      (node (ref "U1") (pin "21") (pinfunction "GND_21") (pintype "passive"))
      (node (ref "U1") (pin "3") (pinfunction "GND_2_3") (pintype "passive"))
      (node (ref "U1") (pin "5") (pinfunction "GND_3_5") (pintype "passive"))
      (node (ref "ULN1") (pin "9") (pinfunction "9_9") (pintype "bidirectional"))
      (node (ref "ULN2") (pin "9") (pinfunction "9_9") (pintype "bidirectional"))
      (node (ref "ULN3") (pin "9") (pinfunction "9_9") (pintype "bidirectional"))
      (node (ref "ULN4") (pin "9") (pinfunction "9_9") (pintype "bidirectional"))
      (node (ref "Y1") (pin "2") (pinfunction "2_2") (pintype "passive"))
    )
    (net (code "51") (name "Net-(BAT1-+)") (class "Default")
      (node (ref "BAT1") (pin "PWR@1") (pinfunction "+_PWR@1") (pintype "power_in"))
      (node (ref "U$1") (pin "3") (pinfunction "VBAT_3") (pintype "bidirectional"))
    )
    (net (code "52") (name "Net-(IC1A-QA)") (class "Default")
      (node (ref "IC1") (pin "15") (pinfunction "QA_15") (pintype "tri_state"))
      (node (ref "ULN1") (pin "1") (pinfunction "1_1") (pintype "bidirectional"))
    )
    (net (code "53") (name "Net-(IC1A-QB)") (class "Default")
      (node (ref "IC1") (pin "1") (pinfunction "QB_1") (pintype "tri_state"))
      (node (ref "ULN1") (pin "2") (pinfunction "2_2") (pintype "bidirectional"))
    )
    (net (code "54") (name "Net-(IC1A-QC)") (class "Default")
      (node (ref "IC1") (pin "2") (pinfunction "QC_2") (pintype "tri_state"))
      (node (ref "ULN1") (pin "3") (pinfunction "3_3") (pintype "bidirectional"))
    )
    (net (code "55") (name "Net-(IC1A-QD)") (class "Default")
      (node (ref "IC1") (pin "3") (pinfunction "QD_3") (pintype "tri_state"))
      (node (ref "ULN1") (pin "4") (pinfunction "4_4") (pintype "bidirectional"))
    )
    (net (code "56") (name "Net-(IC1A-QE)") (class "Default")
      (node (ref "IC1") (pin "4") (pinfunction "QE_4") (pintype "tri_state"))
      (node (ref "ULN1") (pin "5") (pinfunction "5_5") (pintype "bidirectional"))
    )
    (net (code "57") (name "Net-(IC1A-QF)") (class "Default")
      (node (ref "IC1") (pin "5") (pinfunction "QF_5") (pintype "tri_state"))
      (node (ref "ULN1") (pin "6") (pinfunction "6_6") (pintype "bidirectional"))
    )
    (net (code "58") (name "Net-(IC1A-QG)") (class "Default")
      (node (ref "IC1") (pin "6") (pinfunction "QG_6") (pintype "tri_state"))
      (node (ref "ULN1") (pin "7") (pinfunction "7_7") (pintype "bidirectional"))
    )
    (net (code "59") (name "Net-(IC1A-QH)") (class "Default")
      (node (ref "IC1") (pin "7") (pinfunction "QH_7") (pintype "tri_state"))
      (node (ref "ULN1") (pin "8") (pinfunction "8_8") (pintype "bidirectional"))
    )
    (net (code "60") (name "Net-(IC1A-QH*)") (class "Default")
      (node (ref "IC1") (pin "9") (pinfunction "QH*_9") (pintype "tri_state"))
      (node (ref "IC2") (pin "14") (pinfunction "SER_14") (pintype "input"))
    )
    (net (code "61") (name "Net-(IC2A-QA)") (class "Default")
      (node (ref "IC2") (pin "15") (pinfunction "QA_15") (pintype "tri_state"))
      (node (ref "ULN2") (pin "1") (pinfunction "1_1") (pintype "bidirectional"))
    )
    (net (code "62") (name "Net-(IC2A-QB)") (class "Default")
      (node (ref "IC2") (pin "1") (pinfunction "QB_1") (pintype "tri_state"))
      (node (ref "ULN2") (pin "2") (pinfunction "2_2") (pintype "bidirectional"))
    )
    (net (code "63") (name "Net-(IC2A-QC)") (class "Default")
      (node (ref "IC2") (pin "2") (pinfunction "QC_2") (pintype "tri_state"))
      (node (ref "ULN2") (pin "3") (pinfunction "3_3") (pintype "bidirectional"))
    )
    (net (code "64") (name "Net-(IC2A-QD)") (class "Default")
      (node (ref "IC2") (pin "3") (pinfunction "QD_3") (pintype "tri_state"))
      (node (ref "ULN2") (pin "4") (pinfunction "4_4") (pintype "bidirectional"))
    )
    (net (code "65") (name "Net-(IC2A-QE)") (class "Default")
      (node (ref "IC2") (pin "4") (pinfunction "QE_4") (pintype "tri_state"))
      (node (ref "ULN2") (pin "5") (pinfunction "5_5") (pintype "bidirectional"))
    )
    (net (code "66") (name "Net-(IC2A-QF)") (class "Default")
      (node (ref "IC2") (pin "5") (pinfunction "QF_5") (pintype "tri_state"))
      (node (ref "ULN2") (pin "6") (pinfunction "6_6") (pintype "bidirectional"))
    )
    (net (code "67") (name "Net-(IC2A-QG)") (class "Default")
      (node (ref "IC2") (pin "6") (pinfunction "QG_6") (pintype "tri_state"))
      (node (ref "ULN2") (pin "7") (pinfunction "7_7") (pintype "bidirectional"))
    )
    (net (code "68") (name "Net-(IC2A-QH)") (class "Default")
      (node (ref "IC2") (pin "7") (pinfunction "QH_7") (pintype "tri_state"))
      (node (ref "ULN2") (pin "8") (pinfunction "8_8") (pintype "bidirectional"))
    )
    (net (code "69") (name "Net-(IC2A-QH*)") (class "Default")
      (node (ref "IC2") (pin "9") (pinfunction "QH*_9") (pintype "tri_state"))
      (node (ref "IC3") (pin "14") (pinfunction "SER_14") (pintype "input"))
    )
    (net (code "70") (name "Net-(IC3A-QA)") (class "Default")
      (node (ref "IC3") (pin "15") (pinfunction "QA_15") (pintype "tri_state"))
      (node (ref "ULN3") (pin "1") (pinfunction "1_1") (pintype "bidirectional"))
    )
    (net (code "71") (name "Net-(IC3A-QB)") (class "Default")
      (node (ref "IC3") (pin "1") (pinfunction "QB_1") (pintype "tri_state"))
      (node (ref "ULN3") (pin "2") (pinfunction "2_2") (pintype "bidirectional"))
    )
    (net (code "72") (name "Net-(IC3A-QC)") (class "Default")
      (node (ref "IC3") (pin "2") (pinfunction "QC_2") (pintype "tri_state"))
      (node (ref "ULN3") (pin "3") (pinfunction "3_3") (pintype "bidirectional"))
    )
    (net (code "73") (name "Net-(IC3A-QD)") (class "Default")
      (node (ref "IC3") (pin "3") (pinfunction "QD_3") (pintype "tri_state"))
      (node (ref "ULN3") (pin "4") (pinfunction "4_4") (pintype "bidirectional"))
    )
    (net (code "74") (name "Net-(IC3A-QE)") (class "Default")
      (node (ref "IC3") (pin "4") (pinfunction "QE_4") (pintype "tri_state"))
      (node (ref "ULN3") (pin "5") (pinfunction "5_5") (pintype "bidirectional"))
    )
    (net (code "75") (name "Net-(IC3A-QF)") (class "Default")
      (node (ref "IC3") (pin "5") (pinfunction "QF_5") (pintype "tri_state"))
      (node (ref "ULN3") (pin "6") (pinfunction "6_6") (pintype "bidirectional"))
    )
    (net (code "76") (name "Net-(IC3A-QG)") (class "Default")
      (node (ref "IC3") (pin "6") (pinfunction "QG_6") (pintype "tri_state"))
      (node (ref "ULN3") (pin "7") (pinfunction "7_7") (pintype "bidirectional"))
    )
    (net (code "77") (name "Net-(IC3A-QH)") (class "Default")
      (node (ref "IC3") (pin "7") (pinfunction "QH_7") (pintype "tri_state"))
      (node (ref "ULN3") (pin "8") (pinfunction "8_8") (pintype "bidirectional"))
    )
    (net (code "78") (name "Net-(IC3A-QH*)") (class "Default")
      (node (ref "IC3") (pin "9") (pinfunction "QH*_9") (pintype "tri_state"))
      (node (ref "IC4") (pin "14") (pinfunction "SER_14") (pintype "input"))
    )
    (net (code "79") (name "Net-(IC4A-QA)") (class "Default")
      (node (ref "IC4") (pin "15") (pinfunction "QA_15") (pintype "tri_state"))
      (node (ref "ULN4") (pin "1") (pinfunction "1_1") (pintype "bidirectional"))
    )
    (net (code "80") (name "Net-(IC4A-QB)") (class "Default")
      (node (ref "IC4") (pin "1") (pinfunction "QB_1") (pintype "tri_state"))
      (node (ref "ULN4") (pin "2") (pinfunction "2_2") (pintype "bidirectional"))
    )
    (net (code "81") (name "Net-(IC4A-QC)") (class "Default")
      (node (ref "IC4") (pin "2") (pinfunction "QC_2") (pintype "tri_state"))
      (node (ref "ULN4") (pin "3") (pinfunction "3_3") (pintype "bidirectional"))
    )
    (net (code "82") (name "Net-(IC4A-QD)") (class "Default")
      (node (ref "IC4") (pin "3") (pinfunction "QD_3") (pintype "tri_state"))
      (node (ref "ULN4") (pin "4") (pinfunction "4_4") (pintype "bidirectional"))
    )
    (net (code "83") (name "Net-(IC4A-QE)") (class "Default")
      (node (ref "IC4") (pin "4") (pinfunction "QE_4") (pintype "tri_state"))
      (node (ref "ULN4") (pin "5") (pinfunction "5_5") (pintype "bidirectional"))
    )
    (net (code "84") (name "Net-(IC4A-QF)") (class "Default")
      (node (ref "IC4") (pin "5") (pinfunction "QF_5") (pintype "tri_state"))
      (node (ref "ULN4") (pin "6") (pinfunction "6_6") (pintype "bidirectional"))
    )
    (net (code "85") (name "Net-(IC4A-QG)") (class "Default")
      (node (ref "IC4") (pin "6") (pinfunction "QG_6") (pintype "tri_state"))
      (node (ref "ULN4") (pin "7") (pinfunction "7_7") (pintype "bidirectional"))
    )
    (net (code "86") (name "Net-(IC4A-QH)") (class "Default")
      (node (ref "IC4") (pin "7") (pinfunction "QH_7") (pintype "tri_state"))
      (node (ref "ULN4") (pin "8") (pinfunction "8_8") (pintype "bidirectional"))
    )
    (net (code "87") (name "Net-(JP1-Pad1)") (class "Default")
      (node (ref "JP1") (pin "1") (pinfunction "1_1") (pintype "passive"))
      (node (ref "R35") (pin "2") (pinfunction "2_2") (pintype "passive"))
    )
    (net (code "88") (name "Net-(JP1-Pad2)") (class "Default")
      (node (ref "JP1") (pin "2") (pinfunction "2_2") (pintype "passive"))
      (node (ref "R36") (pin "2") (pinfunction "2_2") (pintype "passive"))
    )
    (net (code "89") (name "Net-(JP2-Pad1)") (class "Default")
      (node (ref "JP2") (pin "1") (pinfunction "1_1") (pintype "passive"))
      (node (ref "R37") (pin "2") (pinfunction "2_2") (pintype "passive"))
    )
    (net (code "90") (name "Net-(JP2-Pad2)") (class "Default")
      (node (ref "JP2") (pin "2") (pinfunction "2_2") (pintype "passive"))
      (node (ref "R38") (pin "2") (pinfunction "2_2") (pintype "passive"))
    )
    (net (code "91") (name "Net-(JP3-Pad1)") (class "Default")
      (node (ref "JP3") (pin "1") (pinfunction "1_1") (pintype "passive"))
      (node (ref "R74") (pin "2") (pinfunction "2_2") (pintype "passive"))
    )
    (net (code "92") (name "Net-(JP3-Pad2)") (class "Default")
      (node (ref "JP3") (pin "2") (pinfunction "2_2") (pintype "passive"))
      (node (ref "R75") (pin "2") (pinfunction "2_2") (pintype "passive"))
    )
    (net (code "93") (name "Net-(JP4-Pad1)") (class "Default")
      (node (ref "JP4") (pin "1") (pinfunction "1_1") (pintype "passive"))
      (node (ref "R43") (pin "2") (pinfunction "2_2") (pintype "passive"))
    )
    (net (code "94") (name "Net-(JP4-Pad2)") (class "Default")
      (node (ref "JP4") (pin "2") (pinfunction "2_2") (pintype "passive"))
      (node (ref "R44") (pin "2") (pinfunction "2_2") (pintype "passive"))
    )
    (net (code "95") (name "Net-(JP4-Pad3)") (class "Default")
      (node (ref "JP4") (pin "3") (pinfunction "3_3") (pintype "passive"))
      (node (ref "R45") (pin "2") (pinfunction "2_2") (pintype "passive"))
    )
    (net (code "96") (name "Net-(JP5-Pad1)") (class "Default")
      (node (ref "JP5") (pin "1") (pinfunction "1_1") (pintype "passive"))
      (node (ref "R76") (pin "2") (pinfunction "2_2") (pintype "passive"))
    )
    (net (code "97") (name "Net-(JP5-Pad2)") (class "Default")
      (node (ref "JP5") (pin "2") (pinfunction "2_2") (pintype "passive"))
      (node (ref "R77") (pin "2") (pinfunction "2_2") (pintype "passive"))
    )
    (net (code "98") (name "Net-(JP5-Pad3)") (class "Default")
      (node (ref "JP5") (pin "3") (pinfunction "3_3") (pintype "passive"))
      (node (ref "R78") (pin "2") (pinfunction "2_2") (pintype "passive"))
    )
    (net (code "99") (name "Net-(JP7-Pad1)") (class "Default")
      (node (ref "JP7") (pin "1") (pinfunction "1_1") (pintype "passive"))
      (node (ref "R79") (pin "2") (pinfunction "2_2") (pintype "passive"))
    )
    (net (code "100") (name "Net-(JP7-Pad2)") (class "Default")
      (node (ref "JP7") (pin "2") (pinfunction "2_2") (pintype "passive"))
      (node (ref "R80") (pin "2") (pinfunction "2_2") (pintype "passive"))
    )
    (net (code "101") (name "Net-(JP7-Pad3)") (class "Default")
      (node (ref "JP7") (pin "3") (pinfunction "3_3") (pintype "passive"))
      (node (ref "R81") (pin "2") (pinfunction "2_2") (pintype "passive"))
    )
    (net (code "102") (name "Net-(JP9-Pad1)") (class "Default")
      (node (ref "JP9") (pin "1") (pinfunction "1_1") (pintype "passive"))
      (node (ref "R95") (pin "2") (pinfunction "2_2") (pintype "passive"))
    )
    (net (code "103") (name "Net-(JP9-Pad2)") (class "Default")
      (node (ref "JP9") (pin "2") (pinfunction "2_2") (pintype "passive"))
      (node (ref "R96") (pin "2") (pinfunction "2_2") (pintype "passive"))
    )
    (net (code "104") (name "Net-(JP9-Pad3)") (class "Default")
      (node (ref "JP9") (pin "3") (pinfunction "3_3") (pintype "passive"))
      (node (ref "R97") (pin "2") (pinfunction "2_2") (pintype "passive"))
    )
    (net (code "105") (name "Net-(JP10-Pad1)") (class "Default")
      (node (ref "JP10") (pin "1") (pinfunction "1_1") (pintype "passive"))
      (node (ref "R113") (pin "2") (pinfunction "2_2") (pintype "passive"))
    )
    (net (code "106") (name "Net-(JP10-Pad2)") (class "Default")
      (node (ref "JP10") (pin "2") (pinfunction "2_2") (pintype "passive"))
      (node (ref "R114") (pin "2") (pinfunction "2_2") (pintype "passive"))
    )
    (net (code "107") (name "Net-(JP10-Pad3)") (class "Default")
      (node (ref "JP10") (pin "3") (pinfunction "3_3") (pintype "passive"))
      (node (ref "R115") (pin "2") (pinfunction "2_2") (pintype "passive"))
    )
    (net (code "108") (name "Net-(JP11-Pad1)") (class "Default")
      (node (ref "JP11") (pin "1") (pinfunction "1_1") (pintype "passive"))
      (node (ref "R39") (pin "2") (pinfunction "2_2") (pintype "passive"))
    )
    (net (code "109") (name "Net-(JP11-Pad2)") (class "Default")
      (node (ref "JP11") (pin "2") (pinfunction "2_2") (pintype "passive"))
      (node (ref "R40") (pin "2") (pinfunction "2_2") (pintype "passive"))
    )
    (net (code "110") (name "Net-(JP11-Pad3)") (class "Default")
      (node (ref "JP11") (pin "3") (pinfunction "3_3") (pintype "passive"))
      (node (ref "R41") (pin "2") (pinfunction "2_2") (pintype "passive"))
    )
    (net (code "111") (name "Net-(JP11-Pad4)") (class "Default")
      (node (ref "JP11") (pin "4") (pinfunction "4_4") (pintype "passive"))
      (node (ref "R42") (pin "2") (pinfunction "2_2") (pintype "passive"))
    )
    (net (code "112") (name "Net-(JP12-Pad1)") (class "Default")
      (node (ref "JP12") (pin "1") (pinfunction "1_1") (pintype "passive"))
      (node (ref "R59") (pin "2") (pinfunction "2_2") (pintype "passive"))
    )
    (net (code "113") (name "Net-(JP12-Pad2)") (class "Default")
      (node (ref "JP12") (pin "2") (pinfunction "2_2") (pintype "passive"))
      (node (ref "R60") (pin "2") (pinfunction "2_2") (pintype "passive"))
    )
    (net (code "114") (name "Net-(JP12-Pad3)") (class "Default")
      (node (ref "JP12") (pin "3") (pinfunction "3_3") (pintype "passive"))
      (node (ref "R61") (pin "2") (pinfunction "2_2") (pintype "passive"))
    )
    (net (code "115") (name "Net-(JP12-Pad4)") (class "Default")
      (node (ref "JP12") (pin "4") (pinfunction "4_4") (pintype "passive"))
      (node (ref "R62") (pin "2") (pinfunction "2_2") (pintype "passive"))
    )
    (net (code "116") (name "Net-(JP13-Pad1)") (class "Default")
      (node (ref "JP13") (pin "1") (pinfunction "1_1") (pintype "passive"))
      (node (ref "R63") (pin "2") (pinfunction "2_2") (pintype "passive"))
    )
    (net (code "117") (name "Net-(JP13-Pad2)") (class "Default")
      (node (ref "JP13") (pin "2") (pinfunction "2_2") (pintype "passive"))
      (node (ref "R64") (pin "2") (pinfunction "2_2") (pintype "passive"))
    )
    (net (code "118") (name "Net-(JP13-Pad3)") (class "Default")
      (node (ref "JP13") (pin "3") (pinfunction "3_3") (pintype "passive"))
      (node (ref "R65") (pin "2") (pinfunction "2_2") (pintype "passive"))
    )
    (net (code "119") (name "Net-(JP13-Pad4)") (class "Default")
      (node (ref "JP13") (pin "4") (pinfunction "4_4") (pintype "passive"))
      (node (ref "R66") (pin "2") (pinfunction "2_2") (pintype "passive"))
    )
    (net (code "120") (name "Net-(JP14-Pad1)") (class "Default")
      (node (ref "JP14") (pin "1") (pinfunction "1_1") (pintype "passive"))
      (node (ref "R87") (pin "2") (pinfunction "2_2") (pintype "passive"))
    )
    (net (code "121") (name "Net-(JP14-Pad2)") (class "Default")
      (node (ref "JP14") (pin "2") (pinfunction "2_2") (pintype "passive"))
      (node (ref "R88") (pin "2") (pinfunction "2_2") (pintype "passive"))
    )
    (net (code "122") (name "Net-(JP14-Pad3)") (class "Default")
      (node (ref "JP14") (pin "3") (pinfunction "3_3") (pintype "passive"))
      (node (ref "R89") (pin "2") (pinfunction "2_2") (pintype "passive"))
    )
    (net (code "123") (name "Net-(JP14-Pad4)") (class "Default")
      (node (ref "JP14") (pin "4") (pinfunction "4_4") (pintype "passive"))
      (node (ref "R90") (pin "2") (pinfunction "2_2") (pintype "passive"))
    )
    (net (code "124") (name "Net-(JP15-Pad1)") (class "Default")
      (node (ref "JP15") (pin "1") (pinfunction "1_1") (pintype "passive"))
      (node (ref "R91") (pin "2") (pinfunction "2_2") (pintype "passive"))
    )
    (net (code "125") (name "Net-(JP15-Pad2)") (class "Default")
      (node (ref "JP15") (pin "2") (pinfunction "2_2") (pintype "passive"))
      (node (ref "R92") (pin "2") (pinfunction "2_2") (pintype "passive"))
    )
    (net (code "126") (name "Net-(JP15-Pad3)") (class "Default")
      (node (ref "JP15") (pin "3") (pinfunction "3_3") (pintype "passive"))
      (node (ref "R93") (pin "2") (pinfunction "2_2") (pintype "passive"))
    )
    (net (code "127") (name "Net-(JP15-Pad4)") (class "Default")
      (node (ref "JP15") (pin "4") (pinfunction "4_4") (pintype "passive"))
      (node (ref "R94") (pin "2") (pinfunction "2_2") (pintype "passive"))
    )
    (net (code "128") (name "Net-(JP16-Pad1)") (class "Default")
      (node (ref "JP16") (pin "1") (pinfunction "1_1") (pintype "passive"))
      (node (ref "R109") (pin "2") (pinfunction "2_2") (pintype "passive"))
    )
    (net (code "129") (name "Net-(JP16-Pad2)") (class "Default")
      (node (ref "JP16") (pin "2") (pinfunction "2_2") (pintype "passive"))
      (node (ref "R110") (pin "2") (pinfunction "2_2") (pintype "passive"))
    )
    (net (code "130") (name "Net-(JP16-Pad3)") (class "Default")
      (node (ref "JP16") (pin "3") (pinfunction "3_3") (pintype "passive"))
      (node (ref "R111") (pin "2") (pinfunction "2_2") (pintype "passive"))
    )
    (net (code "131") (name "Net-(JP16-Pad4)") (class "Default")
      (node (ref "JP16") (pin "4") (pinfunction "4_4") (pintype "passive"))
      (node (ref "R112") (pin "2") (pinfunction "2_2") (pintype "passive"))
    )
    (net (code "132") (name "Net-(JP17-Pad1)") (class "Default")
      (node (ref "JP17") (pin "1") (pinfunction "1_1") (pintype "passive"))
      (node (ref "R82") (pin "2") (pinfunction "2_2") (pintype "passive"))
    )
    (net (code "133") (name "Net-(JP17-Pad2)") (class "Default")
      (node (ref "JP17") (pin "2") (pinfunction "2_2") (pintype "passive"))
      (node (ref "R83") (pin "2") (pinfunction "2_2") (pintype "passive"))
    )
    (net (code "134") (name "Net-(JP17-Pad3)") (class "Default")
      (node (ref "JP17") (pin "3") (pinfunction "3_3") (pintype "passive"))
      (node (ref "R84") (pin "2") (pinfunction "2_2") (pintype "passive"))
    )
    (net (code "135") (name "Net-(JP17-Pad4)") (class "Default")
      (node (ref "JP17") (pin "4") (pinfunction "4_4") (pintype "passive"))
      (node (ref "R85") (pin "2") (pinfunction "2_2") (pintype "passive"))
    )
    (net (code "136") (name "Net-(JP17-Pad5)") (class "Default")
      (node (ref "JP17") (pin "5") (pinfunction "5_5") (pintype "passive"))
      (node (ref "R86") (pin "2") (pinfunction "2_2") (pintype "passive"))
    )
    (net (code "137") (name "Net-(JP18-Pad1)") (class "Default")
      (node (ref "JP18") (pin "1") (pinfunction "1_1") (pintype "passive"))
      (node (ref "R104") (pin "2") (pinfunction "2_2") (pintype "passive"))
    )
    (net (code "138") (name "Net-(JP18-Pad2)") (class "Default")
      (node (ref "JP18") (pin "2") (pinfunction "2_2") (pintype "passive"))
      (node (ref "R105") (pin "2") (pinfunction "2_2") (pintype "passive"))
    )
    (net (code "139") (name "Net-(JP18-Pad3)") (class "Default")
      (node (ref "JP18") (pin "3") (pinfunction "3_3") (pintype "passive"))
      (node (ref "R106") (pin "2") (pinfunction "2_2") (pintype "passive"))
    )
    (net (code "140") (name "Net-(JP18-Pad4)") (class "Default")
      (node (ref "JP18") (pin "4") (pinfunction "4_4") (pintype "passive"))
      (node (ref "R107") (pin "2") (pinfunction "2_2") (pintype "passive"))
    )
    (net (code "141") (name "Net-(JP18-Pad5)") (class "Default")
      (node (ref "JP18") (pin "5") (pinfunction "5_5") (pintype "passive"))
      (node (ref "R108") (pin "2") (pinfunction "2_2") (pintype "passive"))
    )
    (net (code "142") (name "Net-(JP19-Pad1)") (class "Default")
      (node (ref "JP19") (pin "1") (pinfunction "1_1") (pintype "passive"))
      (node (ref "R53") (pin "2") (pinfunction "2_2") (pintype "passive"))
    )
    (net (code "143") (name "Net-(JP19-Pad2)") (class "Default")
      (node (ref "JP19") (pin "2") (pinfunction "2_2") (pintype "passive"))
      (node (ref "R54") (pin "2") (pinfunction "2_2") (pintype "passive"))
    )
    (net (code "144") (name "Net-(JP19-Pad3)") (class "Default")
      (node (ref "JP19") (pin "3") (pinfunction "3_3") (pintype "passive"))
      (node (ref "R55") (pin "2") (pinfunction "2_2") (pintype "passive"))
    )
    (net (code "145") (name "Net-(JP19-Pad4)") (class "Default")
      (node (ref "JP19") (pin "4") (pinfunction "4_4") (pintype "passive"))
      (node (ref "R56") (pin "2") (pinfunction "2_2") (pintype "passive"))
    )
    (net (code "146") (name "Net-(JP19-Pad5)") (class "Default")
      (node (ref "JP19") (pin "5") (pinfunction "5_5") (pintype "passive"))
      (node (ref "R57") (pin "2") (pinfunction "2_2") (pintype "passive"))
    )
    (net (code "147") (name "Net-(JP19-Pad6)") (class "Default")
      (node (ref "JP19") (pin "6") (pinfunction "6_6") (pintype "passive"))
      (node (ref "R58") (pin "2") (pinfunction "2_2") (pintype "passive"))
    )
    (net (code "148") (name "Net-(JP20-Pad1)") (class "Default")
      (node (ref "JP20") (pin "1") (pinfunction "1_1") (pintype "passive"))
      (node (ref "R98") (pin "2") (pinfunction "2_2") (pintype "passive"))
    )
    (net (code "149") (name "Net-(JP20-Pad2)") (class "Default")
      (node (ref "JP20") (pin "2") (pinfunction "2_2") (pintype "passive"))
      (node (ref "R99") (pin "2") (pinfunction "2_2") (pintype "passive"))
    )
    (net (code "150") (name "Net-(JP20-Pad3)") (class "Default")
      (node (ref "JP20") (pin "3") (pinfunction "3_3") (pintype "passive"))
      (node (ref "R100") (pin "2") (pinfunction "2_2") (pintype "passive"))
    )
    (net (code "151") (name "Net-(JP20-Pad4)") (class "Default")
      (node (ref "JP20") (pin "4") (pinfunction "4_4") (pintype "passive"))
      (node (ref "R101") (pin "2") (pinfunction "2_2") (pintype "passive"))
    )
    (net (code "152") (name "Net-(JP20-Pad5)") (class "Default")
      (node (ref "JP20") (pin "5") (pinfunction "5_5") (pintype "passive"))
      (node (ref "R102") (pin "2") (pinfunction "2_2") (pintype "passive"))
    )
    (net (code "153") (name "Net-(JP21-Pad1)") (class "Default")
      (node (ref "JP21") (pin "1") (pinfunction "1_1") (pintype "passive"))
      (node (ref "R116") (pin "2") (pinfunction "2_2") (pintype "passive"))
    )
    (net (code "154") (name "Net-(JP21-Pad2)") (class "Default")
      (node (ref "JP21") (pin "2") (pinfunction "2_2") (pintype "passive"))
      (node (ref "R117") (pin "2") (pinfunction "2_2") (pintype "passive"))
    )
    (net (code "155") (name "Net-(JP21-Pad3)") (class "Default")
      (node (ref "JP21") (pin "3") (pinfunction "3_3") (pintype "passive"))
      (node (ref "R118") (pin "2") (pinfunction "2_2") (pintype "passive"))
    )
    (net (code "156") (name "Net-(JP21-Pad4)") (class "Default")
      (node (ref "JP21") (pin "4") (pinfunction "4_4") (pintype "passive"))
      (node (ref "R119") (pin "2") (pinfunction "2_2") (pintype "passive"))
    )
    (net (code "157") (name "Net-(JP21-Pad5)") (class "Default")
      (node (ref "JP21") (pin "5") (pinfunction "5_5") (pintype "passive"))
      (node (ref "R120") (pin "2") (pinfunction "2_2") (pintype "passive"))
    )
    (net (code "158") (name "Net-(JP21-Pad6)") (class "Default")
      (node (ref "JP21") (pin "6") (pinfunction "6_6") (pintype "passive"))
      (node (ref "R121") (pin "2") (pinfunction "2_2") (pintype "passive"))
    )
    (net (code "159") (name "Net-(JP22-Pad1)") (class "Default")
      (node (ref "JP22") (pin "1") (pinfunction "1_1") (pintype "passive"))
      (node (ref "R122") (pin "2") (pinfunction "2_2") (pintype "passive"))
    )
    (net (code "160") (name "Net-(JP22-Pad2)") (class "Default")
      (node (ref "JP22") (pin "2") (pinfunction "2_2") (pintype "passive"))
      (node (ref "R123") (pin "2") (pinfunction "2_2") (pintype "passive"))
    )
    (net (code "161") (name "Net-(JP22-Pad3)") (class "Default")
      (node (ref "JP22") (pin "3") (pinfunction "3_3") (pintype "passive"))
      (node (ref "R124") (pin "2") (pinfunction "2_2") (pintype "passive"))
    )
    (net (code "162") (name "Net-(JP22-Pad4)") (class "Default")
      (node (ref "JP22") (pin "4") (pinfunction "4_4") (pintype "passive"))
      (node (ref "R125") (pin "2") (pinfunction "2_2") (pintype "passive"))
    )
    (net (code "163") (name "Net-(JP22-Pad5)") (class "Default")
      (node (ref "JP22") (pin "5") (pinfunction "5_5") (pintype "passive"))
      (node (ref "R126") (pin "2") (pinfunction "2_2") (pintype "passive"))
    )
    (net (code "164") (name "Net-(JP22-Pad6)") (class "Default")
      (node (ref "JP22") (pin "6") (pinfunction "6_6") (pintype "passive"))
      (node (ref "R127") (pin "2") (pinfunction "2_2") (pintype "passive"))
    )
    (net (code "165") (name "Net-(JP23-Pad1)") (class "Default")
      (node (ref "JP23") (pin "1") (pinfunction "1_1") (pintype "passive"))
      (node (ref "R128") (pin "2") (pinfunction "2_2") (pintype "passive"))
    )
    (net (code "166") (name "Net-(JP23-Pad2)") (class "Default")
      (node (ref "JP23") (pin "2") (pinfunction "2_2") (pintype "passive"))
      (node (ref "R129") (pin "2") (pinfunction "2_2") (pintype "passive"))
    )
    (net (code "167") (name "Net-(JP23-Pad3)") (class "Default")
      (node (ref "JP23") (pin "3") (pinfunction "3_3") (pintype "passive"))
      (node (ref "R130") (pin "2") (pinfunction "2_2") (pintype "passive"))
    )
    (net (code "168") (name "Net-(JP23-Pad4)") (class "Default")
      (node (ref "JP23") (pin "4") (pinfunction "4_4") (pintype "passive"))
      (node (ref "R131") (pin "2") (pinfunction "2_2") (pintype "passive"))
    )
    (net (code "169") (name "Net-(JP23-Pad5)") (class "Default")
      (node (ref "JP23") (pin "5") (pinfunction "5_5") (pintype "passive"))
      (node (ref "R132") (pin "2") (pinfunction "2_2") (pintype "passive"))
    )
    (net (code "170") (name "Net-(JP23-Pad6)") (class "Default")
      (node (ref "JP23") (pin "6") (pinfunction "6_6") (pintype "passive"))
      (node (ref "R133") (pin "2") (pinfunction "2_2") (pintype "passive"))
    )
    (net (code "171") (name "Net-(JP24-Pad1)") (class "Default")
      (node (ref "JP24") (pin "1") (pinfunction "1_1") (pintype "passive"))
      (node (ref "R67") (pin "2") (pinfunction "2_2") (pintype "passive"))
    )
    (net (code "172") (name "Net-(JP24-Pad2)") (class "Default")
      (node (ref "JP24") (pin "2") (pinfunction "2_2") (pintype "passive"))
      (node (ref "R68") (pin "2") (pinfunction "2_2") (pintype "passive"))
    )
    (net (code "173") (name "Net-(JP24-Pad3)") (class "Default")
      (node (ref "JP24") (pin "3") (pinfunction "3_3") (pintype "passive"))
      (node (ref "R69") (pin "2") (pinfunction "2_2") (pintype "passive"))
    )
    (net (code "174") (name "Net-(JP24-Pad4)") (class "Default")
      (node (ref "JP24") (pin "4") (pinfunction "4_4") (pintype "passive"))
      (node (ref "R70") (pin "2") (pinfunction "2_2") (pintype "passive"))
    )
    (net (code "175") (name "Net-(JP24-Pad5)") (class "Default")
      (node (ref "JP24") (pin "5") (pinfunction "5_5") (pintype "passive"))
      (node (ref "R71") (pin "2") (pinfunction "2_2") (pintype "passive"))
    )
    (net (code "176") (name "Net-(JP24-Pad6)") (class "Default")
      (node (ref "JP24") (pin "6") (pinfunction "6_6") (pintype "passive"))
      (node (ref "R72") (pin "2") (pinfunction "2_2") (pintype "passive"))
    )
    (net (code "177") (name "Net-(JP24-Pad7)") (class "Default")
      (node (ref "JP24") (pin "7") (pinfunction "7_7") (pintype "passive"))
      (node (ref "R73") (pin "2") (pinfunction "2_2") (pintype "passive"))
    )
    (net (code "178") (name "Net-(JP25-Pad1)") (class "Default")
      (node (ref "JP25") (pin "1") (pinfunction "1_1") (pintype "passive"))
      (node (ref "R46") (pin "2") (pinfunction "2_2") (pintype "passive"))
    )
    (net (code "179") (name "Net-(JP25-Pad2)") (class "Default")
      (node (ref "JP25") (pin "2") (pinfunction "2_2") (pintype "passive"))
      (node (ref "R47") (pin "2") (pinfunction "2_2") (pintype "passive"))
    )
    (net (code "180") (name "Net-(JP25-Pad3)") (class "Default")
      (node (ref "JP25") (pin "3") (pinfunction "3_3") (pintype "passive"))
      (node (ref "R48") (pin "2") (pinfunction "2_2") (pintype "passive"))
    )
    (net (code "181") (name "Net-(JP25-Pad4)") (class "Default")
      (node (ref "JP25") (pin "4") (pinfunction "4_4") (pintype "passive"))
      (node (ref "R49") (pin "2") (pinfunction "2_2") (pintype "passive"))
    )
    (net (code "182") (name "Net-(JP25-Pad5)") (class "Default")
      (node (ref "JP25") (pin "5") (pinfunction "5_5") (pintype "passive"))
      (node (ref "R50") (pin "2") (pinfunction "2_2") (pintype "passive"))
    )
    (net (code "183") (name "Net-(JP25-Pad6)") (class "Default")
      (node (ref "JP25") (pin "6") (pinfunction "6_6") (pintype "passive"))
      (node (ref "R51") (pin "2") (pinfunction "2_2") (pintype "passive"))
    )
    (net (code "184") (name "Net-(JP25-Pad7)") (class "Default")
      (node (ref "JP25") (pin "7") (pinfunction "7_7") (pintype "passive"))
      (node (ref "R52") (pin "2") (pinfunction "2_2") (pintype "passive"))
    )
    (net (code "185") (name "Net-(JP26-Pad2)") (class "Default")
      (node (ref "JP26") (pin "2") (pinfunction "2_2") (pintype "passive"))
      (node (ref "R7") (pin "2") (pinfunction "2_2") (pintype "passive"))
    )
    (net (code "186") (name "Net-(JP37-Pad1)") (class "Default")
      (node (ref "JP37") (pin "1") (pinfunction "1_1") (pintype "passive"))
      (node (ref "ULN3") (pin "11") (pinfunction "11_11") (pintype "bidirectional"))
    )
    (net (code "187") (name "Net-(JP37-Pad2)") (class "Default")
      (node (ref "JP37") (pin "2") (pinfunction "2_2") (pintype "passive"))
      (node (ref "ULN4") (pin "18") (pinfunction "18_18") (pintype "bidirectional"))
    )
    (net (code "188") (name "Net-(JP37-Pad3)") (class "Default")
      (node (ref "JP37") (pin "3") (pinfunction "3_3") (pintype "passive"))
      (node (ref "ULN4") (pin "17") (pinfunction "17_17") (pintype "bidirectional"))
    )
    (net (code "189") (name "Net-(JP37-Pad4)") (class "Default")
      (node (ref "JP37") (pin "4") (pinfunction "4_4") (pintype "passive"))
      (node (ref "ULN4") (pin "16") (pinfunction "16_16") (pintype "bidirectional"))
    )
    (net (code "190") (name "Net-(JP37-Pad5)") (class "Default")
      (node (ref "JP37") (pin "5") (pinfunction "5_5") (pintype "passive"))
      (node (ref "ULN4") (pin "15") (pinfunction "15_15") (pintype "bidirectional"))
    )
    (net (code "191") (name "Net-(JP37-Pad6)") (class "Default")
      (node (ref "JP37") (pin "6") (pinfunction "6_6") (pintype "passive"))
      (node (ref "ULN4") (pin "14") (pinfunction "14_14") (pintype "bidirectional"))
    )
    (net (code "192") (name "Net-(JP37-Pad7)") (class "Default")
      (node (ref "JP37") (pin "7") (pinfunction "7_7") (pintype "passive"))
      (node (ref "ULN4") (pin "13") (pinfunction "13_13") (pintype "bidirectional"))
    )
    (net (code "193") (name "Net-(JP37-Pad8)") (class "Default")
      (node (ref "JP37") (pin "8") (pinfunction "8_8") (pintype "passive"))
      (node (ref "ULN4") (pin "12") (pinfunction "12_12") (pintype "bidirectional"))
    )
    (net (code "194") (name "Net-(JP37-Pad9)") (class "Default")
      (node (ref "JP37") (pin "9") (pinfunction "9_9") (pintype "passive"))
      (node (ref "ULN4") (pin "11") (pinfunction "11_11") (pintype "bidirectional"))
    )
    (net (code "195") (name "Net-(LED1-PadA)") (class "Default")
      (node (ref "LED1") (pin "A") (pinfunction "A_A") (pintype "passive"))
      (node (ref "R1") (pin "1") (pinfunction "1_1") (pintype "passive"))
    )
    (net (code "196") (name "Net-(U$1-X1)") (class "Default")
      (node (ref "U$1") (pin "1") (pinfunction "X1_1") (pintype "bidirectional"))
      (node (ref "U$2") (pin "P$1") (pinfunction "P$1_P$1") (pintype "bidirectional"))
    )
    (net (code "197") (name "Net-(U$1-X2)") (class "Default")
      (node (ref "U$1") (pin "2") (pinfunction "X2_2") (pintype "bidirectional"))
      (node (ref "U$2") (pin "P$4") (pinfunction "P$2_P$4") (pintype "bidirectional"))
    )
    (net (code "198") (name "Net-(U1-PB6)") (class "Default")
      (node (ref "U1") (pin "7") (pinfunction "PB6_7") (pintype "bidirectional"))
      (node (ref "Y1") (pin "1") (pinfunction "1_1") (pintype "passive"))
    )
    (net (code "199") (name "Net-(U1-PB7)") (class "Default")
      (node (ref "U1") (pin "8") (pinfunction "PB7_8") (pintype "bidirectional"))
      (node (ref "Y1") (pin "3") (pinfunction "3_3") (pintype "passive"))
    )
    (net (code "200") (name "unconnected-(IC4A-QH*-Pad9)") (class "Default")
      (node (ref "IC4") (pin "9") (pinfunction "QH*_9") (pintype "tri_state"))
    )
    (net (code "201") (name "unconnected-(U$1-SQW-Pad7)") (class "Default")
      (node (ref "U$1") (pin "7") (pinfunction "SQW_7") (pintype "bidirectional"))
    )
  )
)
